# zx81_SD_12_smd.net
KiCad netlist of a schematic drawn in EAGLE
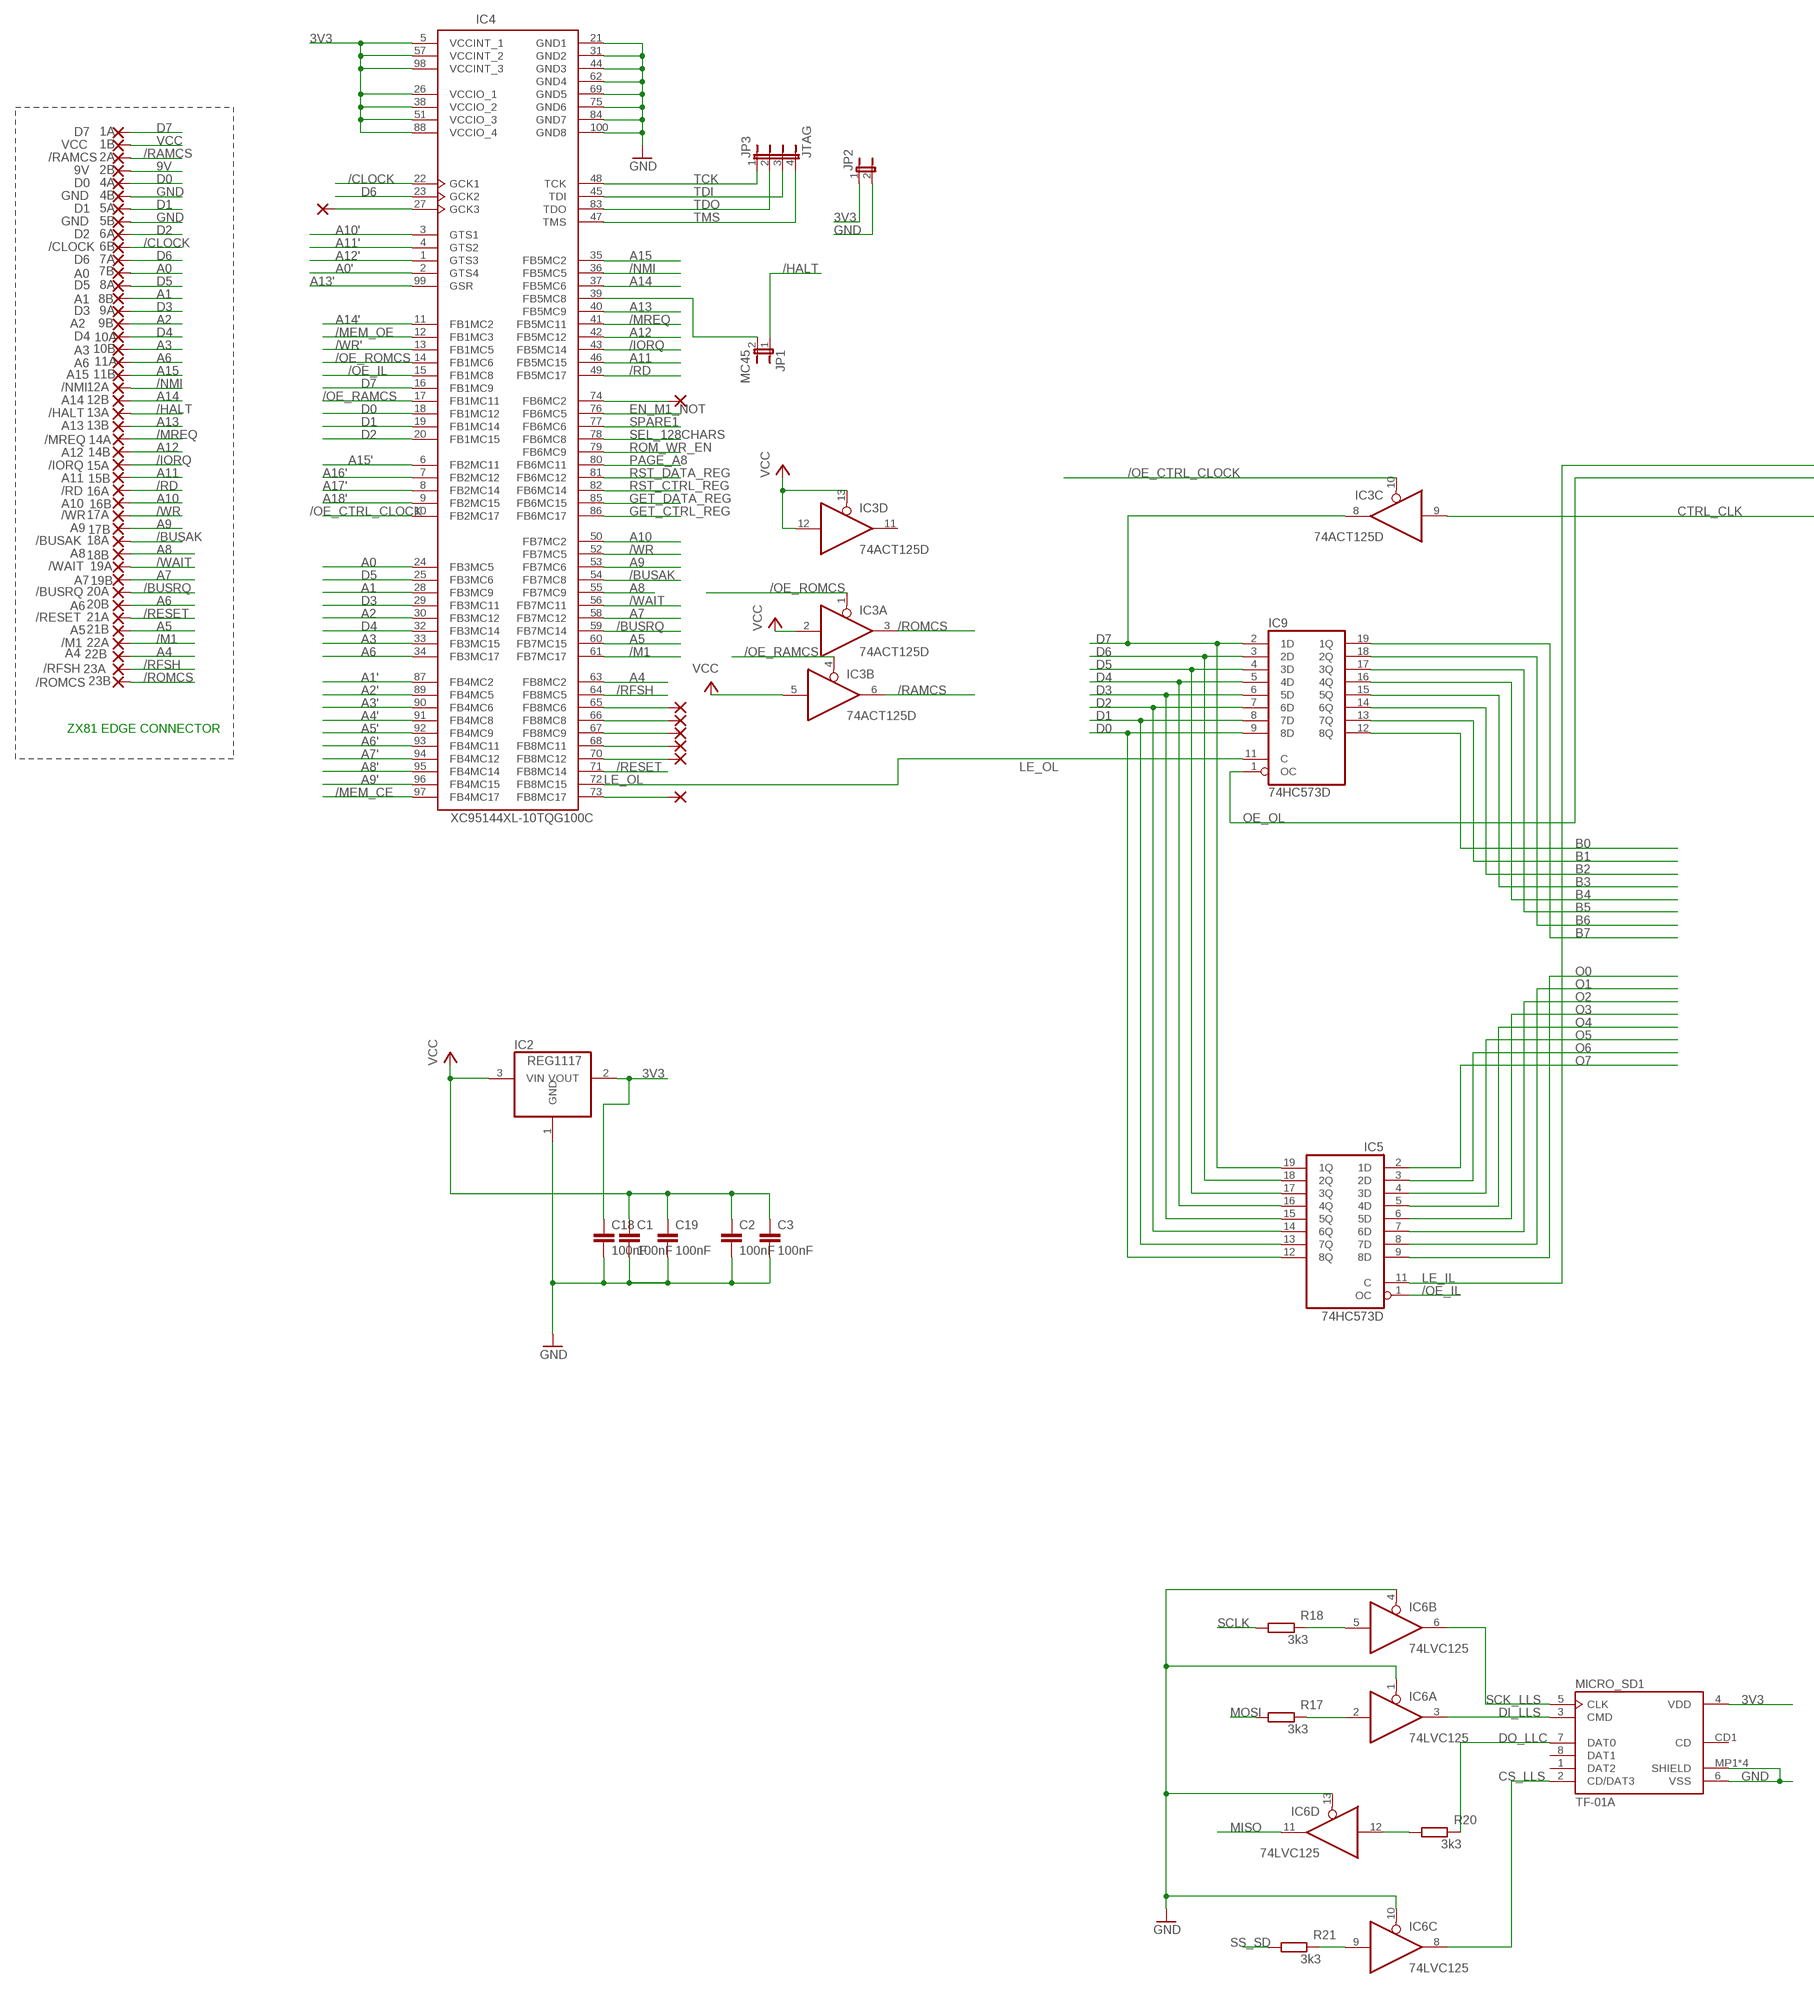
[diagram p0: schematic, sheet 1, part 1 of 2]
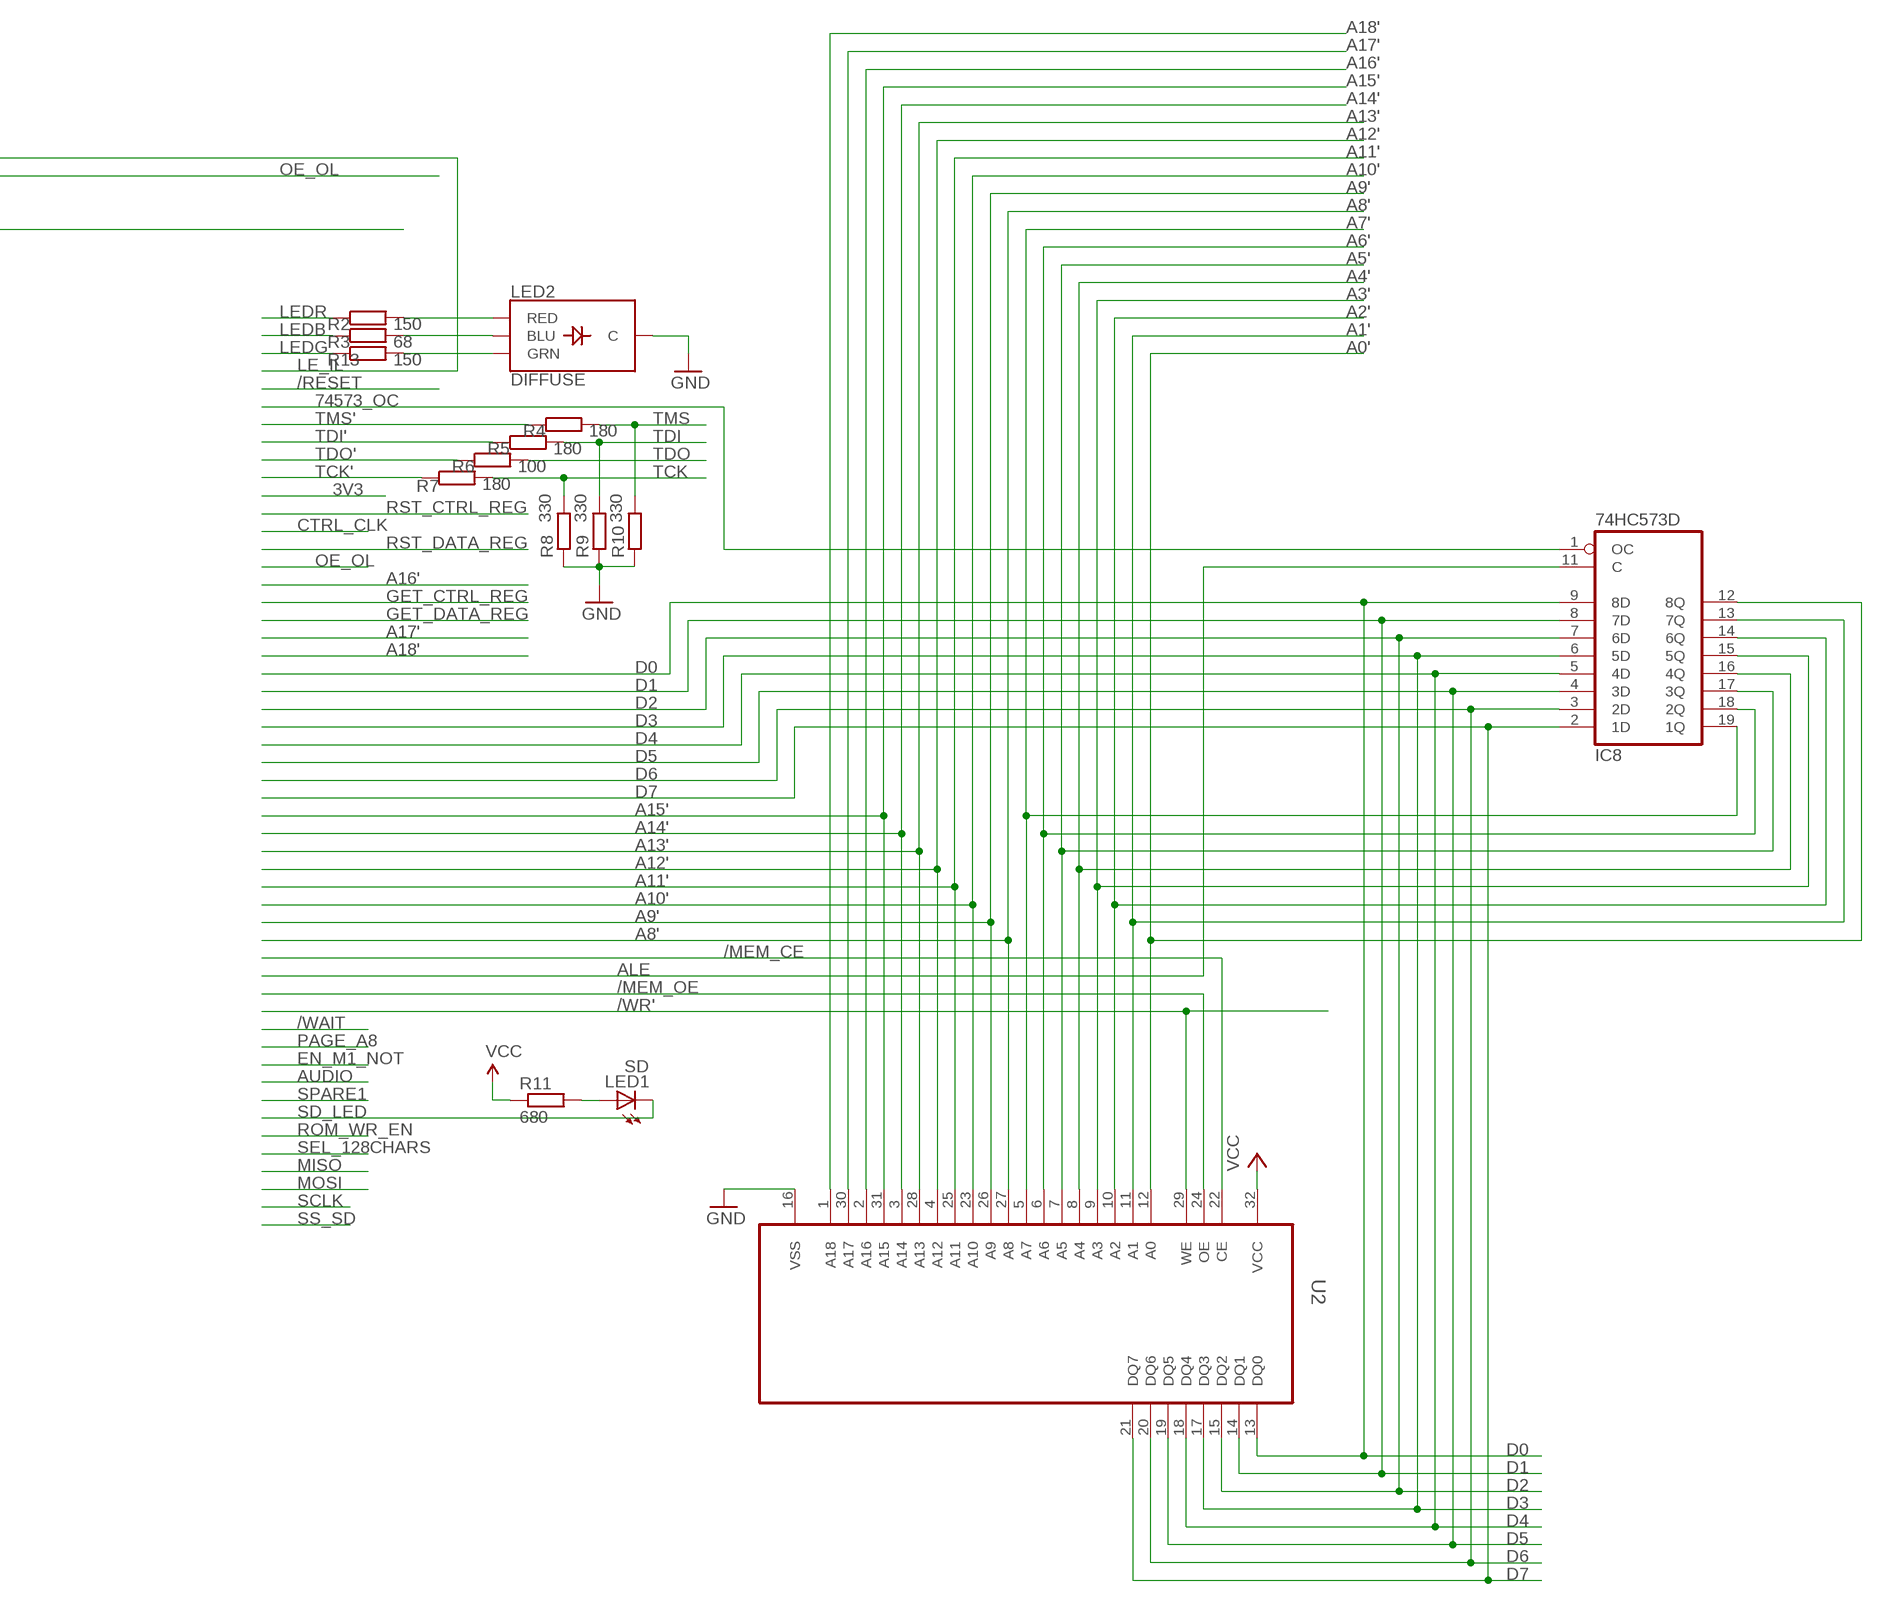
[diagram p1: schematic, sheet 1, part 2 of 2]
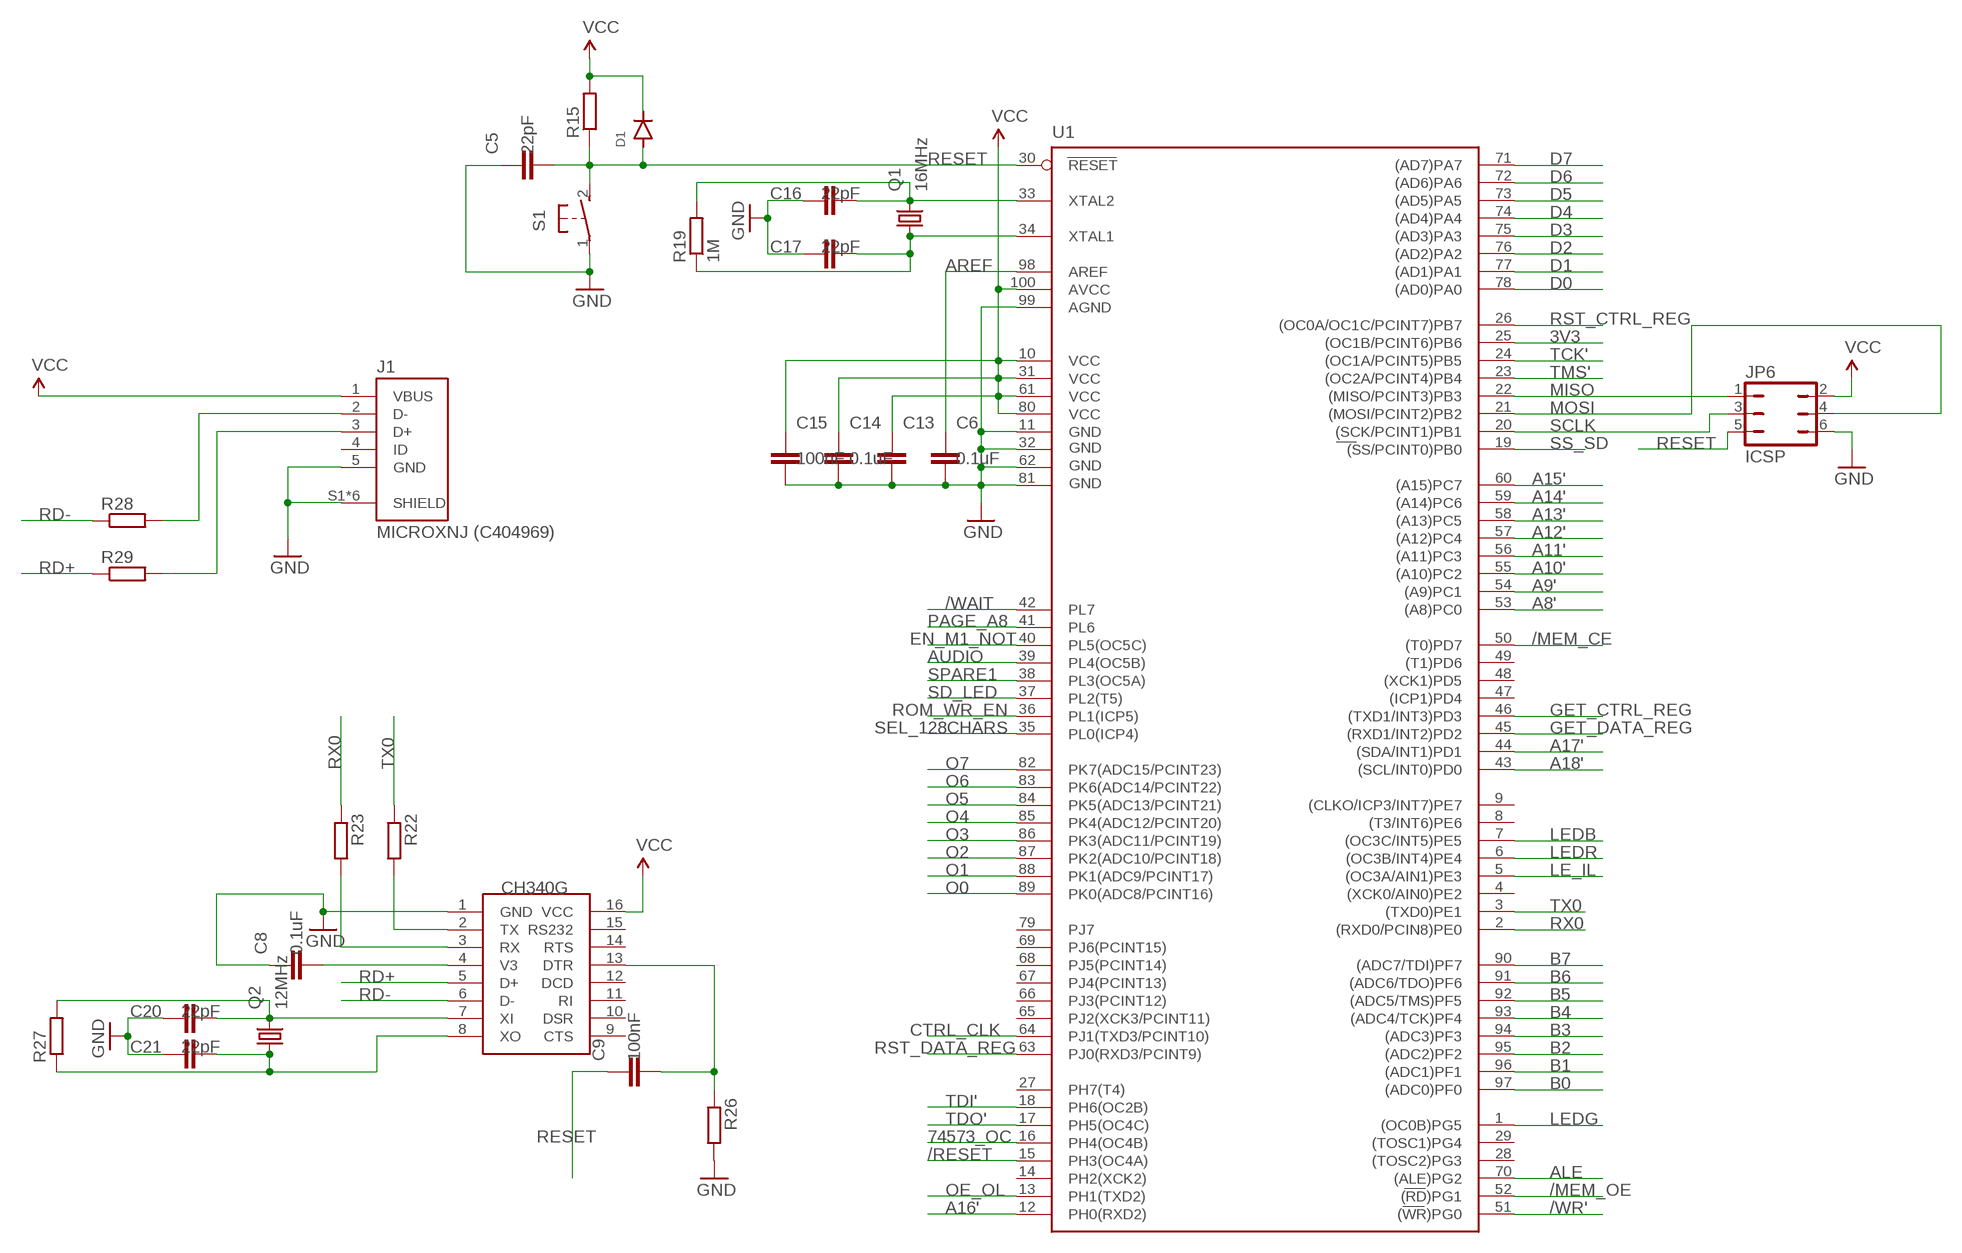
[diagram p2: schematic, sheet 2]

(export (version "E")
  (design (tool "Eeschema 10.0.6"))
  (components
    (comp (ref "1A")
      (value "D7")
      (footprint "eagle-import:EDGEPIN")
      (libsource (lib "eagle-import") (part "SMD2EDGEPIN"))
    )
    (comp (ref "1B")
      (value "VCC")
      (footprint "eagle-import:EDGEPIN")
      (libsource (lib "eagle-import") (part "SMD2EDGEPIN"))
    )
    (comp (ref "2A")
      (value "/RAMCS")
      (footprint "eagle-import:EDGEPIN")
      (libsource (lib "eagle-import") (part "SMD2EDGEPIN"))
    )
    (comp (ref "2B")
      (value "9V")
      (footprint "eagle-import:EDGEPIN")
      (libsource (lib "eagle-import") (part "SMD2EDGEPIN"))
    )
    (comp (ref "4A")
      (value "D0")
      (footprint "eagle-import:EDGEPIN")
      (libsource (lib "eagle-import") (part "SMD2EDGEPIN"))
    )
    (comp (ref "4B")
      (value "GND")
      (footprint "eagle-import:EDGEPIN")
      (libsource (lib "eagle-import") (part "SMD2EDGEPIN"))
    )
    (comp (ref "5A")
      (value "D1")
      (footprint "eagle-import:EDGEPIN")
      (libsource (lib "eagle-import") (part "SMD2EDGEPIN"))
    )
    (comp (ref "5B")
      (value "GND")
      (footprint "eagle-import:EDGEPIN")
      (libsource (lib "eagle-import") (part "SMD2EDGEPIN"))
    )
    (comp (ref "6A")
      (value "D2")
      (footprint "eagle-import:EDGEPIN")
      (libsource (lib "eagle-import") (part "SMD2EDGEPIN"))
    )
    (comp (ref "6B")
      (value "/CLOCK")
      (footprint "eagle-import:EDGEPIN")
      (libsource (lib "eagle-import") (part "SMD2EDGEPIN"))
    )
    (comp (ref "7A")
      (value "D6")
      (footprint "eagle-import:EDGEPIN")
      (libsource (lib "eagle-import") (part "SMD2EDGEPIN"))
    )
    (comp (ref "7B")
      (value "A0")
      (footprint "eagle-import:EDGEPIN")
      (libsource (lib "eagle-import") (part "SMD2EDGEPIN"))
    )
    (comp (ref "8A")
      (value "D5")
      (footprint "eagle-import:EDGEPIN")
      (libsource (lib "eagle-import") (part "SMD2EDGEPIN"))
    )
    (comp (ref "8B")
      (value "A1")
      (footprint "eagle-import:EDGEPIN")
      (libsource (lib "eagle-import") (part "SMD2EDGEPIN"))
    )
    (comp (ref "9A")
      (value "D3")
      (footprint "eagle-import:EDGEPIN")
      (libsource (lib "eagle-import") (part "SMD2EDGEPIN"))
    )
    (comp (ref "9B")
      (value "A2")
      (footprint "eagle-import:EDGEPIN")
      (libsource (lib "eagle-import") (part "SMD2EDGEPIN"))
    )
    (comp (ref "10A")
      (value "D4")
      (footprint "eagle-import:EDGEPIN")
      (libsource (lib "eagle-import") (part "SMD2EDGEPIN"))
    )
    (comp (ref "10B")
      (value "A3")
      (footprint "eagle-import:EDGEPIN")
      (libsource (lib "eagle-import") (part "SMD2EDGEPIN"))
    )
    (comp (ref "11A")
      (value "A6")
      (footprint "eagle-import:EDGEPIN")
      (libsource (lib "eagle-import") (part "SMD2EDGEPIN"))
    )
    (comp (ref "11B")
      (value "A15")
      (footprint "eagle-import:EDGEPIN")
      (libsource (lib "eagle-import") (part "SMD2EDGEPIN"))
    )
    (comp (ref "12A")
      (value "/NMI")
      (footprint "eagle-import:EDGEPIN")
      (libsource (lib "eagle-import") (part "SMD2EDGEPIN"))
    )
    (comp (ref "12B")
      (value "A14")
      (footprint "eagle-import:EDGEPIN")
      (libsource (lib "eagle-import") (part "SMD2EDGEPIN"))
    )
    (comp (ref "13A")
      (value "/HALT")
      (footprint "eagle-import:EDGEPIN")
      (libsource (lib "eagle-import") (part "SMD2EDGEPIN"))
    )
    (comp (ref "13B")
      (value "A13")
      (footprint "eagle-import:EDGEPIN")
      (libsource (lib "eagle-import") (part "SMD2EDGEPIN"))
    )
    (comp (ref "14A")
      (value "/MREQ")
      (footprint "eagle-import:EDGEPIN")
      (libsource (lib "eagle-import") (part "SMD2EDGEPIN"))
    )
    (comp (ref "14B")
      (value "A12")
      (footprint "eagle-import:EDGEPIN")
      (libsource (lib "eagle-import") (part "SMD2EDGEPIN"))
    )
    (comp (ref "15A")
      (value "/IORQ")
      (footprint "eagle-import:EDGEPIN")
      (libsource (lib "eagle-import") (part "SMD2EDGEPIN"))
    )
    (comp (ref "15B")
      (value "A11")
      (footprint "eagle-import:EDGEPIN")
      (libsource (lib "eagle-import") (part "SMD2EDGEPIN"))
    )
    (comp (ref "16A")
      (value "/RD")
      (footprint "eagle-import:EDGEPIN")
      (libsource (lib "eagle-import") (part "SMD2EDGEPIN"))
    )
    (comp (ref "16B")
      (value "A10")
      (footprint "eagle-import:EDGEPIN")
      (libsource (lib "eagle-import") (part "SMD2EDGEPIN"))
    )
    (comp (ref "17A")
      (value "/WR")
      (footprint "eagle-import:EDGEPIN")
      (libsource (lib "eagle-import") (part "SMD2EDGEPIN"))
    )
    (comp (ref "17B")
      (value "A9")
      (footprint "eagle-import:EDGEPIN")
      (libsource (lib "eagle-import") (part "SMD2EDGEPIN"))
    )
    (comp (ref "18A")
      (value "/BUSAK")
      (footprint "eagle-import:EDGEPIN")
      (libsource (lib "eagle-import") (part "SMD2EDGEPIN"))
    )
    (comp (ref "18B")
      (value "A8")
      (footprint "eagle-import:EDGEPIN")
      (libsource (lib "eagle-import") (part "SMD2EDGEPIN"))
    )
    (comp (ref "19A")
      (value "/WAIT")
      (footprint "eagle-import:EDGEPIN")
      (libsource (lib "eagle-import") (part "SMD2EDGEPIN"))
    )
    (comp (ref "19B")
      (value "A7")
      (footprint "eagle-import:EDGEPIN")
      (libsource (lib "eagle-import") (part "SMD2EDGEPIN"))
    )
    (comp (ref "20A")
      (value "/BUSRQ")
      (footprint "eagle-import:EDGEPIN")
      (libsource (lib "eagle-import") (part "SMD2EDGEPIN"))
    )
    (comp (ref "20B")
      (value "A6")
      (footprint "eagle-import:EDGEPIN")
      (libsource (lib "eagle-import") (part "SMD2EDGEPIN"))
    )
    (comp (ref "21A")
      (value "/RESET")
      (footprint "eagle-import:EDGEPIN")
      (libsource (lib "eagle-import") (part "SMD2EDGEPIN"))
    )
    (comp (ref "21B")
      (value "A5")
      (footprint "eagle-import:EDGEPIN")
      (libsource (lib "eagle-import") (part "SMD2EDGEPIN"))
    )
    (comp (ref "22A")
      (value "/M1")
      (footprint "eagle-import:EDGEPIN")
      (libsource (lib "eagle-import") (part "SMD2EDGEPIN"))
    )
    (comp (ref "22B")
      (value "A4")
      (footprint "eagle-import:EDGEPIN")
      (libsource (lib "eagle-import") (part "SMD2EDGEPIN"))
    )
    (comp (ref "23A")
      (value "/RFSH")
      (footprint "eagle-import:EDGEPIN")
      (libsource (lib "eagle-import") (part "SMD2EDGEPIN"))
    )
    (comp (ref "23B")
      (value "/ROMCS")
      (footprint "eagle-import:EDGEPIN")
      (libsource (lib "eagle-import") (part "SMD2EDGEPIN"))
    )
    (comp (ref "C1")
      (value "100nF")
      (footprint "eagle-import:C0603")
      (libsource (lib "eagle-import") (part "C-EUC0603"))
    )
    (comp (ref "C2")
      (value "100nF")
      (footprint "eagle-import:C0603")
      (libsource (lib "eagle-import") (part "C-EUC0603"))
    )
    (comp (ref "C3")
      (value "100nF")
      (footprint "eagle-import:C0603")
      (libsource (lib "eagle-import") (part "C-EUC0603"))
    )
    (comp (ref "C18")
      (value "100nF")
      (footprint "eagle-import:C0603")
      (libsource (lib "eagle-import") (part "C-EUC0603"))
    )
    (comp (ref "C19")
      (value "100nF")
      (footprint "eagle-import:C0603")
      (libsource (lib "eagle-import") (part "C-EUC0603"))
    )
    (comp (ref "IC2")
      (value "REG1117")
      (footprint "eagle-import:SOT223")
      (libsource (lib "eagle-import") (part "REG1117"))
    )
    (comp (ref "IC3")
      (value "74ACT125D")
      (footprint "eagle-import:SO14")
      (libsource (lib "eagle-import") (part "74125DACT"))
    )
    (comp (ref "IC4")
      (value "XC95144XL-10TQG100C")
      (footprint "eagle-import:TQFP100")
      (fields (field (name "MF") "Xilinx Inc."))
      (libsource (lib "eagle-import") (part "XC95144XL-10TQG100C"))
    )
    (comp (ref "IC5")
      (value "74HC573D")
      (footprint "eagle-import:SO20W")
      (libsource (lib "eagle-import") (part "74573DHC"))
    )
    (comp (ref "IC6")
      (value "74LVC125")
      (footprint "eagle-import:SO14")
      (libsource (lib "eagle-import") (part "74125DLS"))
    )
    (comp (ref "IC8")
      (value "74HC573D")
      (footprint "eagle-import:SO20W")
      (libsource (lib "eagle-import") (part "74573DHC"))
    )
    (comp (ref "IC9")
      (value "74HC573D")
      (footprint "eagle-import:SO20W")
      (libsource (lib "eagle-import") (part "74573DHC"))
    )
    (comp (ref "JP1")
      (value "MC45")
      (footprint "eagle-import:JP1")
      (libsource (lib "eagle-import") (part "JP1E"))
    )
    (comp (ref "JP2")
      (value "JP1E")
      (footprint "eagle-import:JP1")
      (libsource (lib "eagle-import") (part "JP1E"))
    )
    (comp (ref "JP3")
      (value "JTAG")
      (footprint "eagle-import:JP4")
      (libsource (lib "eagle-import") (part "JP4E"))
    )
    (comp (ref "LED1")
      (value "SD")
      (footprint "eagle-import:LED5MM")
      (libsource (lib "eagle-import") (part "LED5MM"))
    )
    (comp (ref "LED2")
      (value "DIFFUSE")
      (footprint "eagle-import:LED-RGB-THRU")
      (libsource (lib "eagle-import") (part "LED-RGB-CCDIFFUSE"))
    )
    (comp (ref "MICRO_SD1")
      (value "TF-01A")
      (footprint "eagle-import:TF-01A")
      (fields (field (name "MF") "HRO Electronics Co., Ltd."))
      (libsource (lib "eagle-import") (part "TF-01A"))
    )
    (comp (ref "PAD1")
      (value "1,6/0,8")
      (footprint "eagle-import:1,6_0,8")
      (libsource (lib "eagle-import") (part "1,6/0,8"))
    )
    (comp (ref "PAD2")
      (value "1,6/0,8")
      (footprint "eagle-import:1,6_0,8")
      (libsource (lib "eagle-import") (part "1,6/0,8"))
    )
    (comp (ref "PAD3")
      (value "1,6/0,8")
      (footprint "eagle-import:1,6_0,8")
      (libsource (lib "eagle-import") (part "1,6/0,8"))
    )
    (comp (ref "PAD4")
      (value "1,6/0,8")
      (footprint "eagle-import:1,6_0,8")
      (libsource (lib "eagle-import") (part "1,6/0,8"))
    )
    (comp (ref "PAD5")
      (value "1,6/0,8")
      (footprint "eagle-import:1,6_0,8")
      (libsource (lib "eagle-import") (part "1,6/0,8"))
    )
    (comp (ref "PAD6")
      (value "1,6/0,8")
      (footprint "eagle-import:1,6_0,8")
      (libsource (lib "eagle-import") (part "1,6/0,8"))
    )
    (comp (ref "PAD7")
      (value "1,6/0,8")
      (footprint "eagle-import:1,6_0,8")
      (libsource (lib "eagle-import") (part "1,6/0,8"))
    )
    (comp (ref "PAD8")
      (value "1,6/0,8")
      (footprint "eagle-import:1,6_0,8")
      (libsource (lib "eagle-import") (part "1,6/0,8"))
    )
    (comp (ref "R2")
      (value "150")
      (footprint "eagle-import:R0603")
      (libsource (lib "eagle-import") (part "rcl_334_R-EU_R0603"))
    )
    (comp (ref "R3")
      (value "68")
      (footprint "eagle-import:R0603")
      (libsource (lib "eagle-import") (part "rcl_334_R-EU_R0603"))
    )
    (comp (ref "R4")
      (value "180")
      (footprint "eagle-import:R0603")
      (libsource (lib "eagle-import") (part "rcl_334_R-EU_R0603"))
    )
    (comp (ref "R5")
      (value "180")
      (footprint "eagle-import:R0603")
      (libsource (lib "eagle-import") (part "rcl_334_R-EU_R0603"))
    )
    (comp (ref "R6")
      (value "100")
      (footprint "eagle-import:R0603")
      (libsource (lib "eagle-import") (part "rcl_334_R-EU_R0603"))
    )
    (comp (ref "R7")
      (value "180")
      (footprint "eagle-import:R0603")
      (libsource (lib "eagle-import") (part "rcl_334_R-EU_R0603"))
    )
    (comp (ref "R8")
      (value "330")
      (footprint "eagle-import:R0603")
      (libsource (lib "eagle-import") (part "rcl_334_R-EU_R0603"))
    )
    (comp (ref "R9")
      (value "330")
      (footprint "eagle-import:R0603")
      (libsource (lib "eagle-import") (part "rcl_334_R-EU_R0603"))
    )
    (comp (ref "R10")
      (value "330")
      (footprint "eagle-import:R0603")
      (libsource (lib "eagle-import") (part "rcl_334_R-EU_R0603"))
    )
    (comp (ref "R11")
      (value "680")
      (footprint "eagle-import:R0603")
      (libsource (lib "eagle-import") (part "R-EU_R0603"))
    )
    (comp (ref "R13")
      (value "150")
      (footprint "eagle-import:R0603")
      (libsource (lib "eagle-import") (part "rcl_334_R-EU_R0603"))
    )
    (comp (ref "R17")
      (value "3k3")
      (footprint "eagle-import:R0603")
      (libsource (lib "eagle-import") (part "R-EU_R0603"))
    )
    (comp (ref "R18")
      (value "3k3")
      (footprint "eagle-import:R0603")
      (libsource (lib "eagle-import") (part "R-EU_R0603"))
    )
    (comp (ref "R20")
      (value "3k3")
      (footprint "eagle-import:R0603")
      (libsource (lib "eagle-import") (part "R-EU_R0603"))
    )
    (comp (ref "R21")
      (value "3k3")
      (footprint "eagle-import:R0603")
      (libsource (lib "eagle-import") (part "R-EU_R0603"))
    )
    (comp (ref "U2")
      (value "AS6C4008-55SINSOP5")
      (footprint "eagle-import:SOP32-5")
      (libsource (lib "eagle-import") (part "AS6C4008-55SINSOP5"))
    )
    (comp (ref "C5")
      (value "22pF")
      (footprint "eagle-import:C0603")
      (libsource (lib "eagle-import") (part "C-EUC0603"))
    )
    (comp (ref "C6")
      (value "0.1uF")
      (footprint "eagle-import:C0603")
      (libsource (lib "eagle-import") (part "C-EUC0603"))
    )
    (comp (ref "C8")
      (value "0.1uF")
      (footprint "eagle-import:C0603")
      (libsource (lib "eagle-import") (part "C-EUC0603"))
    )
    (comp (ref "C9")
      (value "100nF")
      (footprint "eagle-import:C0603")
      (libsource (lib "eagle-import") (part "C-EUC0603"))
    )
    (comp (ref "C13")
      (value "0.1uF")
      (footprint "eagle-import:C0603")
      (libsource (lib "eagle-import") (part "C-EUC0603"))
    )
    (comp (ref "C14")
      (value "0.1uF")
      (footprint "eagle-import:C0603")
      (libsource (lib "eagle-import") (part "C-EUC0603"))
    )
    (comp (ref "C15")
      (value "100nF")
      (footprint "eagle-import:C0603")
      (libsource (lib "eagle-import") (part "C-EUC0603"))
    )
    (comp (ref "C16")
      (value "22pF")
      (footprint "eagle-import:C0603")
      (libsource (lib "eagle-import") (part "C-EUC0603"))
    )
    (comp (ref "C17")
      (value "22pF")
      (footprint "eagle-import:C0603")
      (libsource (lib "eagle-import") (part "C-EUC0603"))
    )
    (comp (ref "C20")
      (value "22pF")
      (footprint "eagle-import:C0603")
      (libsource (lib "eagle-import") (part "C-EUC0603"))
    )
    (comp (ref "C21")
      (value "22pF")
      (footprint "eagle-import:C0603")
      (libsource (lib "eagle-import") (part "C-EUC0603"))
    )
    (comp (ref "D1")
      (value "DIODE-SOD123")
      (footprint "eagle-import:SOD123")
      (libsource (lib "eagle-import") (part "DIODE-SOD123"))
    )
    (comp (ref "IC7")
      (value "CH340G")
      (footprint "eagle-import:SOIC16")
      (libsource (lib "eagle-import") (part "CH340G"))
    )
    (comp (ref "J1")
      (value "MICROXNJ (C404969)")
      (footprint "eagle-import:SHOUHAN_MICROXNJ")
      (fields (field (name "MF") "Shouhan") (field (name "MP") "MICROXNJ"))
      (libsource (lib "eagle-import") (part "MICROXNJ"))
    )
    (comp (ref "JP6")
      (value "ICSP")
      (footprint "eagle-import:JP3Q")
      (libsource (lib "eagle-import") (part "JP3Q"))
    )
    (comp (ref "Q1")
      (value "16MHz")
      (footprint "eagle-import:3.2X2.5_KX-7")
      (libsource (lib "eagle-import") (part "KX-7"))
    )
    (comp (ref "Q2")
      (value "12MHz")
      (footprint "eagle-import:3.2X2.5_KX-7")
      (libsource (lib "eagle-import") (part "KX-7"))
    )
    (comp (ref "R15")
      (value "R-EU_R0603")
      (footprint "eagle-import:R0603")
      (libsource (lib "eagle-import") (part "rcl_334_R-EU_R0603"))
    )
    (comp (ref "R19")
      (value "1M")
      (footprint "eagle-import:R0603")
      (libsource (lib "eagle-import") (part "rcl_334_R-EU_R0603"))
    )
    (comp (ref "R22")
      (value "1K")
      (footprint "eagle-import:R0603")
      (libsource (lib "eagle-import") (part "rcl_334_R-EU_R0603"))
    )
    (comp (ref "R23")
      (value "1K")
      (footprint "eagle-import:R0603")
      (libsource (lib "eagle-import") (part "rcl_334_R-EU_R0603"))
    )
    (comp (ref "R26")
      (value "1K")
      (footprint "eagle-import:R0603")
      (libsource (lib "eagle-import") (part "rcl_334_R-EU_R0603"))
    )
    (comp (ref "R27")
      (value "1M")
      (footprint "eagle-import:R0603")
      (libsource (lib "eagle-import") (part "rcl_334_R-EU_R0603"))
    )
    (comp (ref "R28")
      (value "22R")
      (footprint "eagle-import:R0603")
      (libsource (lib "eagle-import") (part "rcl_334_R-EU_R0603"))
    )
    (comp (ref "R29")
      (value "22R")
      (footprint "eagle-import:R0603")
      (libsource (lib "eagle-import") (part "rcl_334_R-EU_R0603"))
    )
    (comp (ref "S1")
      (value "31-XX")
      (footprint "eagle-import:B3F-31XX")
      (fields (field (name "MPN") "B3F-3100"))
      (libsource (lib "eagle-import") (part "31-XX"))
    )
    (comp (ref "U1")
      (value "ATMEGA2560AU")
      (footprint "eagle-import:TQFP100")
      (libsource (lib "eagle-import") (part "ATMEGA2560AU"))
    )
  )
  (nets
    (net (code "1") (name "3V3") (class "Default")
      (node (ref "C18") (pin "1") (pinfunction "1_1") (pintype "passive"))
      (node (ref "IC2") (pin "2") (pinfunction "VOUT_2") (pintype "output"))
      (node (ref "IC4") (pin "26") (pinfunction "VCCIO_1_26") (pintype "power_in"))
      (node (ref "IC4") (pin "38") (pinfunction "VCCIO_2_38") (pintype "power_in"))
      (node (ref "IC4") (pin "5") (pinfunction "VCCINT_1_5") (pintype "power_in"))
      (node (ref "IC4") (pin "51") (pinfunction "VCCIO_3_51") (pintype "power_in"))
      (node (ref "IC4") (pin "57") (pinfunction "VCCINT_2_57") (pintype "power_in"))
      (node (ref "IC4") (pin "88") (pinfunction "VCCIO_4_88") (pintype "power_in"))
      (node (ref "IC4") (pin "98") (pinfunction "VCCINT_3_98") (pintype "power_in"))
      (node (ref "JP2") (pin "1") (pinfunction "1_1") (pintype "passive"))
      (node (ref "MICRO_SD1") (pin "4") (pinfunction "VDD_4") (pintype "power_in"))
      (node (ref "U1") (pin "25") (pinfunction "(OC1B/PCINT6)PB6_25") (pintype "bidirectional"))
    )
    (net (code "2") (name "9V") (class "Default")
      (node (ref "2B") (pin "1") (pinfunction "P_1") (pintype "passive"))
    )
    (net (code "3") (name "74573_OC") (class "Default")
      (node (ref "IC8") (pin "1") (pinfunction "OC_1") (pintype "input"))
      (node (ref "U1") (pin "16") (pinfunction "PH4(OC4B)_16") (pintype "bidirectional"))
    )
    (net (code "4") (name "A0") (class "Default")
      (node (ref "7B") (pin "1") (pinfunction "P_1") (pintype "passive"))
      (node (ref "IC4") (pin "24") (pinfunction "FB3MC5_24") (pintype "bidirectional"))
    )
    (net (code "5") (name "A0'") (class "Default")
      (node (ref "IC4") (pin "2") (pinfunction "GTS4_2") (pintype "bidirectional"))
      (node (ref "IC8") (pin "12") (pinfunction "8Q_12") (pintype "tri_state"))
      (node (ref "U2") (pin "12") (pinfunction "A0_12") (pintype "input"))
    )
    (net (code "6") (name "A1") (class "Default")
      (node (ref "8B") (pin "1") (pinfunction "P_1") (pintype "passive"))
      (node (ref "IC4") (pin "28") (pinfunction "FB3MC9_28") (pintype "bidirectional"))
    )
    (net (code "7") (name "A1'") (class "Default")
      (node (ref "IC4") (pin "87") (pinfunction "FB4MC2_87") (pintype "bidirectional"))
      (node (ref "IC8") (pin "13") (pinfunction "7Q_13") (pintype "tri_state"))
      (node (ref "U2") (pin "11") (pinfunction "A1_11") (pintype "input"))
    )
    (net (code "8") (name "A2") (class "Default")
      (node (ref "9B") (pin "1") (pinfunction "P_1") (pintype "passive"))
      (node (ref "IC4") (pin "30") (pinfunction "FB3MC12_30") (pintype "bidirectional"))
    )
    (net (code "9") (name "A2'") (class "Default")
      (node (ref "IC4") (pin "89") (pinfunction "FB4MC5_89") (pintype "bidirectional"))
      (node (ref "IC8") (pin "14") (pinfunction "6Q_14") (pintype "tri_state"))
      (node (ref "U2") (pin "10") (pinfunction "A2_10") (pintype "input"))
    )
    (net (code "10") (name "A3") (class "Default")
      (node (ref "10B") (pin "1") (pinfunction "P_1") (pintype "passive"))
      (node (ref "IC4") (pin "33") (pinfunction "FB3MC15_33") (pintype "bidirectional"))
    )
    (net (code "11") (name "A3'") (class "Default")
      (node (ref "IC4") (pin "90") (pinfunction "FB4MC6_90") (pintype "bidirectional"))
      (node (ref "IC8") (pin "15") (pinfunction "5Q_15") (pintype "tri_state"))
      (node (ref "U2") (pin "9") (pinfunction "A3_9") (pintype "input"))
    )
    (net (code "12") (name "A4") (class "Default")
      (node (ref "22B") (pin "1") (pinfunction "P_1") (pintype "passive"))
      (node (ref "IC4") (pin "63") (pinfunction "FB8MC2_63") (pintype "bidirectional"))
    )
    (net (code "13") (name "A4'") (class "Default")
      (node (ref "IC4") (pin "91") (pinfunction "FB4MC8_91") (pintype "bidirectional"))
      (node (ref "IC8") (pin "16") (pinfunction "4Q_16") (pintype "tri_state"))
      (node (ref "U2") (pin "8") (pinfunction "A4_8") (pintype "input"))
    )
    (net (code "14") (name "A5") (class "Default")
      (node (ref "21B") (pin "1") (pinfunction "P_1") (pintype "passive"))
      (node (ref "IC4") (pin "60") (pinfunction "FB7MC15_60") (pintype "bidirectional"))
    )
    (net (code "15") (name "A5'") (class "Default")
      (node (ref "IC4") (pin "92") (pinfunction "FB4MC9_92") (pintype "bidirectional"))
      (node (ref "IC8") (pin "17") (pinfunction "3Q_17") (pintype "tri_state"))
      (node (ref "U2") (pin "7") (pinfunction "A5_7") (pintype "input"))
    )
    (net (code "16") (name "A6") (class "Default")
      (node (ref "11A") (pin "1") (pinfunction "P_1") (pintype "passive"))
      (node (ref "20B") (pin "1") (pinfunction "P_1") (pintype "passive"))
      (node (ref "IC4") (pin "34") (pinfunction "FB3MC17_34") (pintype "bidirectional"))
    )
    (net (code "17") (name "A6'") (class "Default")
      (node (ref "IC4") (pin "93") (pinfunction "FB4MC11_93") (pintype "bidirectional"))
      (node (ref "IC8") (pin "18") (pinfunction "2Q_18") (pintype "tri_state"))
      (node (ref "U2") (pin "6") (pinfunction "A6_6") (pintype "input"))
    )
    (net (code "18") (name "A7") (class "Default")
      (node (ref "19B") (pin "1") (pinfunction "P_1") (pintype "passive"))
      (node (ref "IC4") (pin "58") (pinfunction "FB7MC12_58") (pintype "bidirectional"))
    )
    (net (code "19") (name "A7'") (class "Default")
      (node (ref "IC4") (pin "94") (pinfunction "FB4MC12_94") (pintype "bidirectional"))
      (node (ref "IC8") (pin "19") (pinfunction "1Q_19") (pintype "tri_state"))
      (node (ref "U2") (pin "5") (pinfunction "A7_5") (pintype "input"))
    )
    (net (code "20") (name "A8") (class "Default")
      (node (ref "18B") (pin "1") (pinfunction "P_1") (pintype "passive"))
      (node (ref "IC4") (pin "55") (pinfunction "FB7MC9_55") (pintype "bidirectional"))
    )
    (net (code "21") (name "A8'") (class "Default")
      (node (ref "IC4") (pin "95") (pinfunction "FB4MC14_95") (pintype "bidirectional"))
      (node (ref "U1") (pin "53") (pinfunction "(A8)PC0_53") (pintype "bidirectional"))
      (node (ref "U2") (pin "27") (pinfunction "A8_27") (pintype "input"))
    )
    (net (code "22") (name "A9") (class "Default")
      (node (ref "17B") (pin "1") (pinfunction "P_1") (pintype "passive"))
      (node (ref "IC4") (pin "53") (pinfunction "FB7MC6_53") (pintype "bidirectional"))
    )
    (net (code "23") (name "A9'") (class "Default")
      (node (ref "IC4") (pin "96") (pinfunction "FB4MC15_96") (pintype "bidirectional"))
      (node (ref "U1") (pin "54") (pinfunction "(A9)PC1_54") (pintype "bidirectional"))
      (node (ref "U2") (pin "26") (pinfunction "A9_26") (pintype "input"))
    )
    (net (code "24") (name "A10") (class "Default")
      (node (ref "16B") (pin "1") (pinfunction "P_1") (pintype "passive"))
      (node (ref "IC4") (pin "50") (pinfunction "FB7MC2_50") (pintype "bidirectional"))
    )
    (net (code "25") (name "A10'") (class "Default")
      (node (ref "IC4") (pin "3") (pinfunction "GTS1_3") (pintype "bidirectional"))
      (node (ref "U1") (pin "55") (pinfunction "(A10)PC2_55") (pintype "bidirectional"))
      (node (ref "U2") (pin "23") (pinfunction "A10_23") (pintype "input"))
    )
    (net (code "26") (name "A11") (class "Default")
      (node (ref "15B") (pin "1") (pinfunction "P_1") (pintype "passive"))
      (node (ref "IC4") (pin "46") (pinfunction "FB5MC15_46") (pintype "bidirectional"))
    )
    (net (code "27") (name "A11'") (class "Default")
      (node (ref "IC4") (pin "4") (pinfunction "GTS2_4") (pintype "bidirectional"))
      (node (ref "U1") (pin "56") (pinfunction "(A11)PC3_56") (pintype "bidirectional"))
      (node (ref "U2") (pin "25") (pinfunction "A11_25") (pintype "input"))
    )
    (net (code "28") (name "A12") (class "Default")
      (node (ref "14B") (pin "1") (pinfunction "P_1") (pintype "passive"))
      (node (ref "IC4") (pin "42") (pinfunction "FB5MC12_42") (pintype "bidirectional"))
    )
    (net (code "29") (name "A12'") (class "Default")
      (node (ref "IC4") (pin "1") (pinfunction "GTS3_1") (pintype "bidirectional"))
      (node (ref "U1") (pin "57") (pinfunction "(A12)PC4_57") (pintype "bidirectional"))
      (node (ref "U2") (pin "4") (pinfunction "A12_4") (pintype "input"))
    )
    (net (code "30") (name "A13") (class "Default")
      (node (ref "13B") (pin "1") (pinfunction "P_1") (pintype "passive"))
      (node (ref "IC4") (pin "40") (pinfunction "FB5MC9_40") (pintype "bidirectional"))
    )
    (net (code "31") (name "A13'") (class "Default")
      (node (ref "IC4") (pin "99") (pinfunction "GSR_99") (pintype "bidirectional"))
      (node (ref "U1") (pin "58") (pinfunction "(A13)PC5_58") (pintype "bidirectional"))
      (node (ref "U2") (pin "28") (pinfunction "A13_28") (pintype "input"))
    )
    (net (code "32") (name "A14") (class "Default")
      (node (ref "12B") (pin "1") (pinfunction "P_1") (pintype "passive"))
      (node (ref "IC4") (pin "37") (pinfunction "FB5MC6_37") (pintype "bidirectional"))
    )
    (net (code "33") (name "A14'") (class "Default")
      (node (ref "IC4") (pin "11") (pinfunction "FB1MC2_11") (pintype "bidirectional"))
      (node (ref "U1") (pin "59") (pinfunction "(A14)PC6_59") (pintype "bidirectional"))
      (node (ref "U2") (pin "3") (pinfunction "A14_3") (pintype "input"))
    )
    (net (code "34") (name "A15") (class "Default")
      (node (ref "11B") (pin "1") (pinfunction "P_1") (pintype "passive"))
      (node (ref "IC4") (pin "35") (pinfunction "FB5MC2_35") (pintype "bidirectional"))
    )
    (net (code "35") (name "A15'") (class "Default")
      (node (ref "IC4") (pin "6") (pinfunction "FB2MC11_6") (pintype "bidirectional"))
      (node (ref "U1") (pin "60") (pinfunction "(A15)PC7_60") (pintype "bidirectional"))
      (node (ref "U2") (pin "31") (pinfunction "A15_31") (pintype "input"))
    )
    (net (code "36") (name "A16'") (class "Default")
      (node (ref "IC4") (pin "7") (pinfunction "FB2MC12_7") (pintype "bidirectional"))
      (node (ref "U1") (pin "12") (pinfunction "PH0(RXD2)_12") (pintype "bidirectional"))
      (node (ref "U2") (pin "2") (pinfunction "A16_2") (pintype "input"))
    )
    (net (code "37") (name "A17'") (class "Default")
      (node (ref "IC4") (pin "8") (pinfunction "FB2MC14_8") (pintype "bidirectional"))
      (node (ref "U1") (pin "44") (pinfunction "(SDA/INT1)PD1_44") (pintype "bidirectional"))
      (node (ref "U2") (pin "30") (pinfunction "A17_30") (pintype "input"))
    )
    (net (code "38") (name "A18'") (class "Default")
      (node (ref "IC4") (pin "9") (pinfunction "FB2MC15_9") (pintype "bidirectional"))
      (node (ref "U1") (pin "43") (pinfunction "(SCL/INT0)PD0_43") (pintype "bidirectional"))
      (node (ref "U2") (pin "1") (pinfunction "A18_1") (pintype "input"))
    )
    (net (code "39") (name "ALE") (class "Default")
      (node (ref "IC8") (pin "11") (pinfunction "C_11") (pintype "input"))
      (node (ref "U1") (pin "70") (pinfunction "(ALE)PG2_70") (pintype "bidirectional"))
    )
    (net (code "40") (name "AREF") (class "Default")
      (node (ref "C6") (pin "1") (pinfunction "1_1") (pintype "passive"))
      (node (ref "U1") (pin "98") (pinfunction "AREF_98") (pintype "bidirectional"))
    )
    (net (code "41") (name "AUDIO") (class "Default")
      (node (ref "U1") (pin "39") (pinfunction "PL4(OC5B)_39") (pintype "bidirectional"))
    )
    (net (code "42") (name "B0") (class "Default")
      (node (ref "IC9") (pin "19") (pinfunction "1Q_19") (pintype "tri_state"))
      (node (ref "U1") (pin "97") (pinfunction "(ADC0)PF0_97") (pintype "bidirectional"))
    )
    (net (code "43") (name "B1") (class "Default")
      (node (ref "IC9") (pin "18") (pinfunction "2Q_18") (pintype "tri_state"))
      (node (ref "U1") (pin "96") (pinfunction "(ADC1)PF1_96") (pintype "bidirectional"))
    )
    (net (code "44") (name "B2") (class "Default")
      (node (ref "IC9") (pin "17") (pinfunction "3Q_17") (pintype "tri_state"))
      (node (ref "U1") (pin "95") (pinfunction "(ADC2)PF2_95") (pintype "bidirectional"))
    )
    (net (code "45") (name "B3") (class "Default")
      (node (ref "IC9") (pin "16") (pinfunction "4Q_16") (pintype "tri_state"))
      (node (ref "U1") (pin "94") (pinfunction "(ADC3)PF3_94") (pintype "bidirectional"))
    )
    (net (code "46") (name "B4") (class "Default")
      (node (ref "IC9") (pin "15") (pinfunction "5Q_15") (pintype "tri_state"))
      (node (ref "U1") (pin "93") (pinfunction "(ADC4/TCK)PF4_93") (pintype "bidirectional"))
    )
    (net (code "47") (name "B5") (class "Default")
      (node (ref "IC9") (pin "14") (pinfunction "6Q_14") (pintype "tri_state"))
      (node (ref "U1") (pin "92") (pinfunction "(ADC5/TMS)PF5_92") (pintype "bidirectional"))
    )
    (net (code "48") (name "B6") (class "Default")
      (node (ref "IC9") (pin "13") (pinfunction "7Q_13") (pintype "tri_state"))
      (node (ref "U1") (pin "91") (pinfunction "(ADC6/TDO)PF6_91") (pintype "bidirectional"))
    )
    (net (code "49") (name "B7") (class "Default")
      (node (ref "IC9") (pin "12") (pinfunction "8Q_12") (pintype "tri_state"))
      (node (ref "U1") (pin "90") (pinfunction "(ADC7/TDI)PF7_90") (pintype "bidirectional"))
    )
    (net (code "50") (name "CS_LLS") (class "Default")
      (node (ref "IC6") (pin "8") (pinfunction "O_8") (pintype "tri_state"))
      (node (ref "MICRO_SD1") (pin "2") (pinfunction "CD/DAT3_2") (pintype "bidirectional"))
    )
    (net (code "51") (name "CTRL_CLK") (class "Default")
      (node (ref "IC3") (pin "9") (pinfunction "I_9") (pintype "input"))
      (node (ref "U1") (pin "64") (pinfunction "PJ1(TXD3/PCINT10)_64") (pintype "bidirectional"))
    )
    (net (code "52") (name "D0") (class "Default")
      (node (ref "4A") (pin "1") (pinfunction "P_1") (pintype "passive"))
      (node (ref "IC4") (pin "18") (pinfunction "FB1MC12_18") (pintype "bidirectional"))
      (node (ref "IC5") (pin "12") (pinfunction "8Q_12") (pintype "tri_state"))
      (node (ref "IC8") (pin "9") (pinfunction "8D_9") (pintype "input"))
      (node (ref "IC9") (pin "9") (pinfunction "8D_9") (pintype "input"))
      (node (ref "U1") (pin "78") (pinfunction "(AD0)PA0_78") (pintype "bidirectional"))
      (node (ref "U2") (pin "13") (pinfunction "DQ0_13") (pintype "output"))
    )
    (net (code "53") (name "D1") (class "Default")
      (node (ref "5A") (pin "1") (pinfunction "P_1") (pintype "passive"))
      (node (ref "IC4") (pin "19") (pinfunction "FB1MC14_19") (pintype "bidirectional"))
      (node (ref "IC5") (pin "13") (pinfunction "7Q_13") (pintype "tri_state"))
      (node (ref "IC8") (pin "8") (pinfunction "7D_8") (pintype "input"))
      (node (ref "IC9") (pin "8") (pinfunction "7D_8") (pintype "input"))
      (node (ref "U1") (pin "77") (pinfunction "(AD1)PA1_77") (pintype "bidirectional"))
      (node (ref "U2") (pin "14") (pinfunction "DQ1_14") (pintype "output"))
    )
    (net (code "54") (name "D2") (class "Default")
      (node (ref "6A") (pin "1") (pinfunction "P_1") (pintype "passive"))
      (node (ref "IC4") (pin "20") (pinfunction "FB1MC15_20") (pintype "bidirectional"))
      (node (ref "IC5") (pin "14") (pinfunction "6Q_14") (pintype "tri_state"))
      (node (ref "IC8") (pin "7") (pinfunction "6D_7") (pintype "input"))
      (node (ref "IC9") (pin "7") (pinfunction "6D_7") (pintype "input"))
      (node (ref "U1") (pin "76") (pinfunction "(AD2)PA2_76") (pintype "bidirectional"))
      (node (ref "U2") (pin "15") (pinfunction "DQ2_15") (pintype "output"))
    )
    (net (code "55") (name "D3") (class "Default")
      (node (ref "9A") (pin "1") (pinfunction "P_1") (pintype "passive"))
      (node (ref "IC4") (pin "29") (pinfunction "FB3MC11_29") (pintype "bidirectional"))
      (node (ref "IC5") (pin "15") (pinfunction "5Q_15") (pintype "tri_state"))
      (node (ref "IC8") (pin "6") (pinfunction "5D_6") (pintype "input"))
      (node (ref "IC9") (pin "6") (pinfunction "5D_6") (pintype "input"))
      (node (ref "U1") (pin "75") (pinfunction "(AD3)PA3_75") (pintype "bidirectional"))
      (node (ref "U2") (pin "17") (pinfunction "DQ3_17") (pintype "output"))
    )
    (net (code "56") (name "D4") (class "Default")
      (node (ref "10A") (pin "1") (pinfunction "P_1") (pintype "passive"))
      (node (ref "IC4") (pin "32") (pinfunction "FB3MC14_32") (pintype "bidirectional"))
      (node (ref "IC5") (pin "16") (pinfunction "4Q_16") (pintype "tri_state"))
      (node (ref "IC8") (pin "5") (pinfunction "4D_5") (pintype "input"))
      (node (ref "IC9") (pin "5") (pinfunction "4D_5") (pintype "input"))
      (node (ref "U1") (pin "74") (pinfunction "(AD4)PA4_74") (pintype "bidirectional"))
      (node (ref "U2") (pin "18") (pinfunction "DQ4_18") (pintype "output"))
    )
    (net (code "57") (name "D5") (class "Default")
      (node (ref "8A") (pin "1") (pinfunction "P_1") (pintype "passive"))
      (node (ref "IC4") (pin "25") (pinfunction "FB3MC6_25") (pintype "bidirectional"))
      (node (ref "IC5") (pin "17") (pinfunction "3Q_17") (pintype "tri_state"))
      (node (ref "IC8") (pin "4") (pinfunction "3D_4") (pintype "input"))
      (node (ref "IC9") (pin "4") (pinfunction "3D_4") (pintype "input"))
      (node (ref "U1") (pin "73") (pinfunction "(AD5)PA5_73") (pintype "bidirectional"))
      (node (ref "U2") (pin "19") (pinfunction "DQ5_19") (pintype "output"))
    )
    (net (code "58") (name "D6") (class "Default")
      (node (ref "7A") (pin "1") (pinfunction "P_1") (pintype "passive"))
      (node (ref "IC4") (pin "23") (pinfunction "GCK2_23") (pintype "bidirectional"))
      (node (ref "IC5") (pin "18") (pinfunction "2Q_18") (pintype "tri_state"))
      (node (ref "IC8") (pin "3") (pinfunction "2D_3") (pintype "input"))
      (node (ref "IC9") (pin "3") (pinfunction "2D_3") (pintype "input"))
      (node (ref "U1") (pin "72") (pinfunction "(AD6)PA6_72") (pintype "bidirectional"))
      (node (ref "U2") (pin "20") (pinfunction "DQ6_20") (pintype "output"))
    )
    (net (code "59") (name "D7") (class "Default")
      (node (ref "1A") (pin "1") (pinfunction "P_1") (pintype "passive"))
      (node (ref "IC3") (pin "8") (pinfunction "O_8") (pintype "tri_state"))
      (node (ref "IC4") (pin "16") (pinfunction "FB1MC9_16") (pintype "bidirectional"))
      (node (ref "IC5") (pin "19") (pinfunction "1Q_19") (pintype "tri_state"))
      (node (ref "IC8") (pin "2") (pinfunction "1D_2") (pintype "input"))
      (node (ref "IC9") (pin "2") (pinfunction "1D_2") (pintype "input"))
      (node (ref "U1") (pin "71") (pinfunction "(AD7)PA7_71") (pintype "bidirectional"))
      (node (ref "U2") (pin "21") (pinfunction "DQ7_21") (pintype "output"))
    )
    (net (code "60") (name "DI_LLS") (class "Default")
      (node (ref "IC6") (pin "3") (pinfunction "O_3") (pintype "tri_state"))
      (node (ref "MICRO_SD1") (pin "3") (pinfunction "CMD_3") (pintype "bidirectional"))
    )
    (net (code "61") (name "DO_LLC") (class "Default")
      (node (ref "IC6") (pin "12") (pinfunction "I_12") (pintype "input"))
      (node (ref "R20") (pin "1") (pinfunction "1_1") (pintype "passive"))
    )
    (net (code "62") (name "EN_M1_NOT") (class "Default")
      (node (ref "IC4") (pin "76") (pinfunction "FB6MC5_76") (pintype "bidirectional"))
      (node (ref "U1") (pin "40") (pinfunction "PL5(OC5C)_40") (pintype "bidirectional"))
    )
    (net (code "63") (name "GET_CTRL_REG") (class "Default")
      (node (ref "IC4") (pin "86") (pinfunction "FB6MC17_86") (pintype "bidirectional"))
      (node (ref "U1") (pin "46") (pinfunction "(TXD1/INT3)PD3_46") (pintype "bidirectional"))
    )
    (net (code "64") (name "GET_DATA_REG") (class "Default")
      (node (ref "IC4") (pin "85") (pinfunction "FB6MC15_85") (pintype "bidirectional"))
      (node (ref "U1") (pin "45") (pinfunction "(RXD1/INT2)PD2_45") (pintype "bidirectional"))
    )
    (net (code "65") (name "GND") (class "Default")
      (node (ref "4B") (pin "1") (pinfunction "P_1") (pintype "passive"))
      (node (ref "5B") (pin "1") (pinfunction "P_1") (pintype "passive"))
      (node (ref "C1") (pin "2") (pinfunction "2_2") (pintype "passive"))
      (node (ref "C13") (pin "2") (pinfunction "2_2") (pintype "passive"))
      (node (ref "C14") (pin "2") (pinfunction "2_2") (pintype "passive"))
      (node (ref "C15") (pin "2") (pinfunction "2_2") (pintype "passive"))
      (node (ref "C16") (pin "1") (pinfunction "1_1") (pintype "passive"))
      (node (ref "C17") (pin "1") (pinfunction "1_1") (pintype "passive"))
      (node (ref "C18") (pin "2") (pinfunction "2_2") (pintype "passive"))
      (node (ref "C19") (pin "2") (pinfunction "2_2") (pintype "passive"))
      (node (ref "C2") (pin "2") (pinfunction "2_2") (pintype "passive"))
      (node (ref "C20") (pin "1") (pinfunction "1_1") (pintype "passive"))
      (node (ref "C21") (pin "1") (pinfunction "1_1") (pintype "passive"))
      (node (ref "C3") (pin "2") (pinfunction "2_2") (pintype "passive"))
      (node (ref "C5") (pin "1") (pinfunction "1_1") (pintype "passive"))
      (node (ref "C6") (pin "2") (pinfunction "2_2") (pintype "passive"))
      (node (ref "C8") (pin "1") (pinfunction "1_1") (pintype "passive"))
      (node (ref "IC2") (pin "1") (pinfunction "GND_1") (pintype "power_in"))
      (node (ref "IC4") (pin "100") (pinfunction "GND8_100") (pintype "power_in"))
      (node (ref "IC4") (pin "21") (pinfunction "GND1_21") (pintype "power_in"))
      (node (ref "IC4") (pin "31") (pinfunction "GND2_31") (pintype "power_in"))
      (node (ref "IC4") (pin "44") (pinfunction "GND3_44") (pintype "power_in"))
      (node (ref "IC4") (pin "62") (pinfunction "GND4_62") (pintype "power_in"))
      (node (ref "IC4") (pin "69") (pinfunction "GND5_69") (pintype "power_in"))
      (node (ref "IC4") (pin "75") (pinfunction "GND6_75") (pintype "power_in"))
      (node (ref "IC4") (pin "84") (pinfunction "GND7_84") (pintype "power_in"))
      (node (ref "IC6") (pin "1") (pinfunction "OE_1") (pintype "input"))
      (node (ref "IC6") (pin "10") (pinfunction "OE_10") (pintype "input"))
      (node (ref "IC6") (pin "13") (pinfunction "OE_13") (pintype "input"))
      (node (ref "IC6") (pin "4") (pinfunction "OE_4") (pintype "input"))
      (node (ref "IC7") (pin "1") (pinfunction "GND_1") (pintype "bidirectional"))
      (node (ref "J1") (pin "5") (pinfunction "GND_5") (pintype "power_in"))
      (node (ref "J1") (pin "S1") (pinfunction "SHIELD_S1") (pintype "passive"))
      (node (ref "J1") (pin "S2") (pinfunction "SHIELD_S2") (pintype "passive"))
      (node (ref "J1") (pin "S3") (pinfunction "SHIELD_S3") (pintype "passive"))
      (node (ref "J1") (pin "S4") (pinfunction "SHIELD_S4") (pintype "passive"))
      (node (ref "J1") (pin "S5") (pinfunction "SHIELD_S5") (pintype "passive"))
      (node (ref "J1") (pin "S6") (pinfunction "SHIELD_S6") (pintype "passive"))
      (node (ref "JP2") (pin "2") (pinfunction "2_2") (pintype "passive"))
      (node (ref "JP6") (pin "6") (pinfunction "6_6") (pintype "passive"))
      (node (ref "LED2") (pin "2") (pinfunction "C_2") (pintype "bidirectional"))
      (node (ref "MICRO_SD1") (pin "6") (pinfunction "VSS_6") (pintype "power_in"))
      (node (ref "MICRO_SD1") (pin "MP1") (pinfunction "SHIELD_MP1") (pintype "power_in"))
      (node (ref "MICRO_SD1") (pin "MP2") (pinfunction "SHIELD_MP2") (pintype "power_in"))
      (node (ref "MICRO_SD1") (pin "MP3") (pinfunction "SHIELD_MP3") (pintype "power_in"))
      (node (ref "MICRO_SD1") (pin "MP4") (pinfunction "SHIELD_MP4") (pintype "power_in"))
      (node (ref "R10") (pin "1") (pinfunction "1_1") (pintype "passive"))
      (node (ref "R26") (pin "2") (pinfunction "2_2") (pintype "passive"))
      (node (ref "R8") (pin "1") (pinfunction "1_1") (pintype "passive"))
      (node (ref "R9") (pin "1") (pinfunction "1_1") (pintype "passive"))
      (node (ref "S1") (pin "1") (pinfunction "P_1") (pintype "passive"))
      (node (ref "U1") (pin "11") (pinfunction "GND_11") (pintype "power_in"))
      (node (ref "U1") (pin "32") (pinfunction "GND1_32") (pintype "power_in"))
      (node (ref "U1") (pin "62") (pinfunction "GND2_62") (pintype "power_in"))
      (node (ref "U1") (pin "81") (pinfunction "GND3_81") (pintype "power_in"))
      (node (ref "U1") (pin "99") (pinfunction "AGND_99") (pintype "power_in"))
      (node (ref "U2") (pin "16") (pinfunction "VSS_16") (pintype "output"))
    )
    (net (code "66") (name "LEDB") (class "Default")
      (node (ref "R3") (pin "1") (pinfunction "1_1") (pintype "passive"))
      (node (ref "U1") (pin "7") (pinfunction "(OC3C/INT5)PE5_7") (pintype "bidirectional"))
    )
    (net (code "67") (name "LEDG") (class "Default")
      (node (ref "R13") (pin "1") (pinfunction "1_1") (pintype "passive"))
      (node (ref "U1") (pin "1") (pinfunction "(OC0B)PG5_1") (pintype "bidirectional"))
    )
    (net (code "68") (name "LEDR") (class "Default")
      (node (ref "R2") (pin "1") (pinfunction "1_1") (pintype "passive"))
      (node (ref "U1") (pin "6") (pinfunction "(OC3B/INT4)PE4_6") (pintype "bidirectional"))
    )
    (net (code "69") (name "LE_IL") (class "Default")
      (node (ref "IC5") (pin "11") (pinfunction "C_11") (pintype "input"))
      (node (ref "U1") (pin "5") (pinfunction "(OC3A/AIN1)PE3_5") (pintype "bidirectional"))
    )
    (net (code "70") (name "LE_OL") (class "Default")
      (node (ref "IC4") (pin "72") (pinfunction "FB8MC15_72") (pintype "bidirectional"))
      (node (ref "IC9") (pin "11") (pinfunction "C_11") (pintype "input"))
    )
    (net (code "71") (name "MISO") (class "Default")
      (node (ref "IC6") (pin "11") (pinfunction "O_11") (pintype "tri_state"))
      (node (ref "JP6") (pin "1") (pinfunction "1_1") (pintype "passive"))
      (node (ref "U1") (pin "22") (pinfunction "(MISO/PCINT3)PB3_22") (pintype "bidirectional"))
    )
    (net (code "72") (name "MOSI") (class "Default")
      (node (ref "JP6") (pin "4") (pinfunction "4_4") (pintype "passive"))
      (node (ref "R17") (pin "1") (pinfunction "1_1") (pintype "passive"))
      (node (ref "U1") (pin "21") (pinfunction "(MOSI/PCINT2)PB2_21") (pintype "bidirectional"))
    )
    (net (code "73") (name "Net-(IC4-FB5MC8)") (class "Default")
      (node (ref "IC4") (pin "39") (pinfunction "FB5MC8_39") (pintype "bidirectional"))
      (node (ref "JP1") (pin "2") (pinfunction "2_2") (pintype "passive"))
    )
    (net (code "74") (name "Net-(IC4-FB6MC2)") (class "Default")
      (node (ref "IC4") (pin "74") (pinfunction "FB6MC2_74") (pintype "bidirectional"))
      (node (ref "PAD8") (pin "1") (pinfunction "P_1") (pintype "passive"))
    )
    (net (code "75") (name "Net-(IC4-FB8MC6)") (class "Default")
      (node (ref "IC4") (pin "65") (pinfunction "FB8MC6_65") (pintype "bidirectional"))
      (node (ref "PAD2") (pin "1") (pinfunction "P_1") (pintype "passive"))
    )
    (net (code "76") (name "Net-(IC4-FB8MC8)") (class "Default")
      (node (ref "IC4") (pin "66") (pinfunction "FB8MC8_66") (pintype "bidirectional"))
      (node (ref "PAD3") (pin "1") (pinfunction "P_1") (pintype "passive"))
    )
    (net (code "77") (name "Net-(IC4-FB8MC9)") (class "Default")
      (node (ref "IC4") (pin "67") (pinfunction "FB8MC9_67") (pintype "bidirectional"))
      (node (ref "PAD4") (pin "1") (pinfunction "P_1") (pintype "passive"))
    )
    (net (code "78") (name "Net-(IC4-FB8MC11)") (class "Default")
      (node (ref "IC4") (pin "68") (pinfunction "FB8MC11_68") (pintype "bidirectional"))
      (node (ref "PAD5") (pin "1") (pinfunction "P_1") (pintype "passive"))
    )
    (net (code "79") (name "Net-(IC4-FB8MC12)") (class "Default")
      (node (ref "IC4") (pin "70") (pinfunction "FB8MC12_70") (pintype "bidirectional"))
      (node (ref "PAD7") (pin "1") (pinfunction "P_1") (pintype "passive"))
    )
    (net (code "80") (name "Net-(IC4-FB8MC17)") (class "Default")
      (node (ref "IC4") (pin "73") (pinfunction "FB8MC17_73") (pintype "bidirectional"))
      (node (ref "PAD6") (pin "1") (pinfunction "P_1") (pintype "passive"))
    )
    (net (code "81") (name "Net-(IC4-GCK3)") (class "Default")
      (node (ref "IC4") (pin "27") (pinfunction "GCK3_27") (pintype "bidirectional"))
      (node (ref "PAD1") (pin "1") (pinfunction "P_1") (pintype "passive"))
    )
    (net (code "82") (name "Net-(IC6A-I)") (class "Default")
      (node (ref "IC6") (pin "2") (pinfunction "I_2") (pintype "input"))
      (node (ref "R17") (pin "2") (pinfunction "2_2") (pintype "passive"))
    )
    (net (code "83") (name "Net-(IC6B-I)") (class "Default")
      (node (ref "IC6") (pin "5") (pinfunction "I_5") (pintype "input"))
      (node (ref "R18") (pin "2") (pinfunction "2_2") (pintype "passive"))
    )
    (net (code "84") (name "Net-(IC6C-I)") (class "Default")
      (node (ref "IC6") (pin "9") (pinfunction "I_9") (pintype "input"))
      (node (ref "R21") (pin "2") (pinfunction "2_2") (pintype "passive"))
    )
    (net (code "85") (name "Net-(IC7-DTR)") (class "Default")
      (node (ref "C9") (pin "2") (pinfunction "2_2") (pintype "passive"))
      (node (ref "IC7") (pin "13") (pinfunction "DTR_13") (pintype "bidirectional"))
      (node (ref "R26") (pin "1") (pinfunction "1_1") (pintype "passive"))
    )
    (net (code "86") (name "Net-(IC7-RX)") (class "Default")
      (node (ref "IC7") (pin "3") (pinfunction "RX_3") (pintype "bidirectional"))
      (node (ref "R23") (pin "2") (pinfunction "2_2") (pintype "passive"))
    )
    (net (code "87") (name "Net-(IC7-TX)") (class "Default")
      (node (ref "IC7") (pin "2") (pinfunction "TX_2") (pintype "bidirectional"))
      (node (ref "R22") (pin "2") (pinfunction "2_2") (pintype "passive"))
    )
    (net (code "88") (name "Net-(IC7-V3)") (class "Default")
      (node (ref "C8") (pin "2") (pinfunction "2_2") (pintype "passive"))
      (node (ref "IC7") (pin "4") (pinfunction "V3_4") (pintype "bidirectional"))
    )
    (net (code "89") (name "Net-(IC7-XI)") (class "Default")
      (node (ref "C20") (pin "2") (pinfunction "2_2") (pintype "passive"))
      (node (ref "IC7") (pin "7") (pinfunction "XI_7") (pintype "bidirectional"))
      (node (ref "Q2") (pin "3") (pinfunction "2_3") (pintype "passive"))
      (node (ref "R27") (pin "2") (pinfunction "2_2") (pintype "passive"))
    )
    (net (code "90") (name "Net-(IC7-XO)") (class "Default")
      (node (ref "C21") (pin "2") (pinfunction "2_2") (pintype "passive"))
      (node (ref "IC7") (pin "8") (pinfunction "XO_8") (pintype "bidirectional"))
      (node (ref "Q2") (pin "1") (pinfunction "1_1") (pintype "passive"))
      (node (ref "R27") (pin "1") (pinfunction "1_1") (pintype "passive"))
    )
    (net (code "91") (name "Net-(J1-D+)") (class "Default")
      (node (ref "J1") (pin "3") (pinfunction "D+_3") (pintype "bidirectional"))
      (node (ref "R29") (pin "2") (pinfunction "2_2") (pintype "passive"))
    )
    (net (code "92") (name "Net-(J1-D-)") (class "Default")
      (node (ref "J1") (pin "2") (pinfunction "D-_2") (pintype "bidirectional"))
      (node (ref "R28") (pin "2") (pinfunction "2_2") (pintype "passive"))
    )
    (net (code "93") (name "Net-(LED1-PadA)") (class "Default")
      (node (ref "LED1") (pin "A") (pinfunction "A_A") (pintype "passive"))
      (node (ref "R11") (pin "2") (pinfunction "2_2") (pintype "passive"))
    )
    (net (code "94") (name "Net-(LED2-BLU)") (class "Default")
      (node (ref "LED2") (pin "4") (pinfunction "BLU_4") (pintype "bidirectional"))
      (node (ref "R3") (pin "2") (pinfunction "2_2") (pintype "passive"))
    )
    (net (code "95") (name "Net-(LED2-GRN)") (class "Default")
      (node (ref "LED2") (pin "3") (pinfunction "GRN_3") (pintype "bidirectional"))
      (node (ref "R13") (pin "2") (pinfunction "2_2") (pintype "passive"))
    )
    (net (code "96") (name "Net-(LED2-RED)") (class "Default")
      (node (ref "LED2") (pin "1") (pinfunction "RED_1") (pintype "bidirectional"))
      (node (ref "R2") (pin "2") (pinfunction "2_2") (pintype "passive"))
    )
    (net (code "97") (name "Net-(MICRO_SD1-DAT0)") (class "Default")
      (node (ref "MICRO_SD1") (pin "7") (pinfunction "DAT0_7") (pintype "bidirectional"))
      (node (ref "R20") (pin "2") (pinfunction "2_2") (pintype "passive"))
    )
    (net (code "98") (name "Net-(Q1-2)") (class "Default")
      (node (ref "C16") (pin "2") (pinfunction "2_2") (pintype "passive"))
      (node (ref "Q1") (pin "3") (pinfunction "2_3") (pintype "passive"))
      (node (ref "R19") (pin "2") (pinfunction "2_2") (pintype "passive"))
      (node (ref "U1") (pin "33") (pinfunction "XTAL2_33") (pintype "output"))
    )
    (net (code "99") (name "Net-(U1-XTAL1)") (class "Default")
      (node (ref "C17") (pin "2") (pinfunction "2_2") (pintype "passive"))
      (node (ref "Q1") (pin "1") (pinfunction "1_1") (pintype "passive"))
      (node (ref "R19") (pin "1") (pinfunction "1_1") (pintype "passive"))
      (node (ref "U1") (pin "34") (pinfunction "XTAL1_34") (pintype "input"))
    )
    (net (code "100") (name "O0") (class "Default")
      (node (ref "IC5") (pin "2") (pinfunction "1D_2") (pintype "input"))
      (node (ref "U1") (pin "89") (pinfunction "PK0(ADC8/PCINT16)_89") (pintype "bidirectional"))
    )
    (net (code "101") (name "O1") (class "Default")
      (node (ref "IC5") (pin "3") (pinfunction "2D_3") (pintype "input"))
      (node (ref "U1") (pin "88") (pinfunction "PK1(ADC9/PCINT17)_88") (pintype "bidirectional"))
    )
    (net (code "102") (name "O2") (class "Default")
      (node (ref "IC5") (pin "4") (pinfunction "3D_4") (pintype "input"))
      (node (ref "U1") (pin "87") (pinfunction "PK2(ADC10/PCINT18)_87") (pintype "bidirectional"))
    )
    (net (code "103") (name "O3") (class "Default")
      (node (ref "IC5") (pin "5") (pinfunction "4D_5") (pintype "input"))
      (node (ref "U1") (pin "86") (pinfunction "PK3(ADC11/PCINT19)_86") (pintype "bidirectional"))
    )
    (net (code "104") (name "O4") (class "Default")
      (node (ref "IC5") (pin "6") (pinfunction "5D_6") (pintype "input"))
      (node (ref "U1") (pin "85") (pinfunction "PK4(ADC12/PCINT20)_85") (pintype "bidirectional"))
    )
    (net (code "105") (name "O5") (class "Default")
      (node (ref "IC5") (pin "7") (pinfunction "6D_7") (pintype "input"))
      (node (ref "U1") (pin "84") (pinfunction "PK5(ADC13/PCINT21)_84") (pintype "bidirectional"))
    )
    (net (code "106") (name "O6") (class "Default")
      (node (ref "IC5") (pin "8") (pinfunction "7D_8") (pintype "input"))
      (node (ref "U1") (pin "83") (pinfunction "PK6(ADC14/PCINT22)_83") (pintype "bidirectional"))
    )
    (net (code "107") (name "O7") (class "Default")
      (node (ref "IC5") (pin "9") (pinfunction "8D_9") (pintype "input"))
      (node (ref "U1") (pin "82") (pinfunction "PK7(ADC15/PCINT23)_82") (pintype "bidirectional"))
    )
    (net (code "108") (name "OE_OL") (class "Default")
      (node (ref "IC9") (pin "1") (pinfunction "OC_1") (pintype "input"))
      (node (ref "U1") (pin "13") (pinfunction "PH1(TXD2)_13") (pintype "bidirectional"))
    )
    (net (code "109") (name "PAGE_A8") (class "Default")
      (node (ref "IC4") (pin "80") (pinfunction "FB6MC11_80") (pintype "bidirectional"))
      (node (ref "U1") (pin "41") (pinfunction "PL6_41") (pintype "bidirectional"))
    )
    (net (code "110") (name "RD+") (class "Default")
      (node (ref "IC7") (pin "5") (pinfunction "D+_5") (pintype "bidirectional"))
      (node (ref "R29") (pin "1") (pinfunction "1_1") (pintype "passive"))
    )
    (net (code "111") (name "RD-") (class "Default")
      (node (ref "IC7") (pin "6") (pinfunction "D-_6") (pintype "bidirectional"))
      (node (ref "R28") (pin "1") (pinfunction "1_1") (pintype "passive"))
    )
    (net (code "112") (name "RESET") (class "Default")
      (node (ref "C5") (pin "2") (pinfunction "2_2") (pintype "passive"))
      (node (ref "C9") (pin "1") (pinfunction "1_1") (pintype "passive"))
      (node (ref "D1") (pin "A") (pinfunction "A_A") (pintype "passive"))
      (node (ref "JP6") (pin "5") (pinfunction "5_5") (pintype "passive"))
      (node (ref "R15") (pin "1") (pinfunction "1_1") (pintype "passive"))
      (node (ref "S1") (pin "2") (pinfunction "S_2") (pintype "passive"))
      (node (ref "U1") (pin "30") (pinfunction "RESET_30") (pintype "input"))
    )
    (net (code "113") (name "ROM_WR_EN") (class "Default")
      (node (ref "IC4") (pin "79") (pinfunction "FB6MC9_79") (pintype "bidirectional"))
      (node (ref "U1") (pin "36") (pinfunction "PL1(ICP5)_36") (pintype "bidirectional"))
    )
    (net (code "114") (name "RST_CTRL_REG") (class "Default")
      (node (ref "IC4") (pin "82") (pinfunction "FB6MC14_82") (pintype "bidirectional"))
      (node (ref "U1") (pin "26") (pinfunction "(OC0A/OC1C/PCINT7)PB7_26") (pintype "bidirectional"))
    )
    (net (code "115") (name "RST_DATA_REG") (class "Default")
      (node (ref "IC4") (pin "81") (pinfunction "FB6MC12_81") (pintype "bidirectional"))
      (node (ref "U1") (pin "63") (pinfunction "PJ0(RXD3/PCINT9)_63") (pintype "bidirectional"))
    )
    (net (code "116") (name "RX0") (class "Default")
      (node (ref "R23") (pin "1") (pinfunction "1_1") (pintype "passive"))
      (node (ref "U1") (pin "2") (pinfunction "(RXD0/PCIN8)PE0_2") (pintype "bidirectional"))
    )
    (net (code "117") (name "SCK_LLS") (class "Default")
      (node (ref "IC6") (pin "6") (pinfunction "O_6") (pintype "tri_state"))
      (node (ref "MICRO_SD1") (pin "5") (pinfunction "CLK_5") (pintype "bidirectional"))
    )
    (net (code "118") (name "SCLK") (class "Default")
      (node (ref "JP6") (pin "3") (pinfunction "3_3") (pintype "passive"))
      (node (ref "R18") (pin "1") (pinfunction "1_1") (pintype "passive"))
      (node (ref "U1") (pin "20") (pinfunction "(SCK/PCINT1)PB1_20") (pintype "bidirectional"))
    )
    (net (code "119") (name "SD_LED") (class "Default")
      (node (ref "LED1") (pin "K") (pinfunction "C_K") (pintype "passive"))
      (node (ref "U1") (pin "37") (pinfunction "PL2(T5)_37") (pintype "bidirectional"))
    )
    (net (code "120") (name "SEL_128CHARS") (class "Default")
      (node (ref "IC4") (pin "78") (pinfunction "FB6MC8_78") (pintype "bidirectional"))
      (node (ref "U1") (pin "35") (pinfunction "PL0(ICP4)_35") (pintype "bidirectional"))
    )
    (net (code "121") (name "SPARE1") (class "Default")
      (node (ref "IC4") (pin "77") (pinfunction "FB6MC6_77") (pintype "bidirectional"))
      (node (ref "U1") (pin "38") (pinfunction "PL3(OC5A)_38") (pintype "bidirectional"))
    )
    (net (code "122") (name "SS_SD") (class "Default")
      (node (ref "R21") (pin "1") (pinfunction "1_1") (pintype "passive"))
      (node (ref "U1") (pin "19") (pinfunction "(SS/PCINT0)PB0_19") (pintype "bidirectional"))
    )
    (net (code "123") (name "TCK") (class "Default")
      (node (ref "IC4") (pin "48") (pinfunction "TCK_48") (pintype "passive"))
      (node (ref "JP3") (pin "1") (pinfunction "1_1") (pintype "passive"))
      (node (ref "R7") (pin "2") (pinfunction "2_2") (pintype "passive"))
      (node (ref "R8") (pin "2") (pinfunction "2_2") (pintype "passive"))
    )
    (net (code "124") (name "TCK'") (class "Default")
      (node (ref "R7") (pin "1") (pinfunction "1_1") (pintype "passive"))
      (node (ref "U1") (pin "24") (pinfunction "(OC1A/PCINT5)PB5_24") (pintype "bidirectional"))
    )
    (net (code "125") (name "TDI") (class "Default")
      (node (ref "IC4") (pin "45") (pinfunction "TDI_45") (pintype "passive"))
      (node (ref "JP3") (pin "3") (pinfunction "3_3") (pintype "passive"))
      (node (ref "R5") (pin "2") (pinfunction "2_2") (pintype "passive"))
      (node (ref "R9") (pin "2") (pinfunction "2_2") (pintype "passive"))
    )
    (net (code "126") (name "TDI'") (class "Default")
      (node (ref "R5") (pin "1") (pinfunction "1_1") (pintype "passive"))
      (node (ref "U1") (pin "18") (pinfunction "PH6(OC2B)_18") (pintype "bidirectional"))
    )
    (net (code "127") (name "TDO") (class "Default")
      (node (ref "IC4") (pin "83") (pinfunction "TDO_83") (pintype "passive"))
      (node (ref "JP3") (pin "2") (pinfunction "2_2") (pintype "passive"))
      (node (ref "R6") (pin "2") (pinfunction "2_2") (pintype "passive"))
    )
    (net (code "128") (name "TDO'") (class "Default")
      (node (ref "R6") (pin "1") (pinfunction "1_1") (pintype "passive"))
      (node (ref "U1") (pin "17") (pinfunction "PH5(OC4C)_17") (pintype "bidirectional"))
    )
    (net (code "129") (name "TMS") (class "Default")
      (node (ref "IC4") (pin "47") (pinfunction "TMS_47") (pintype "passive"))
      (node (ref "JP3") (pin "4") (pinfunction "4_4") (pintype "passive"))
      (node (ref "R10") (pin "2") (pinfunction "2_2") (pintype "passive"))
      (node (ref "R4") (pin "2") (pinfunction "2_2") (pintype "passive"))
    )
    (net (code "130") (name "TMS'") (class "Default")
      (node (ref "R4") (pin "1") (pinfunction "1_1") (pintype "passive"))
      (node (ref "U1") (pin "23") (pinfunction "(OC2A/PCINT4)PB4_23") (pintype "bidirectional"))
    )
    (net (code "131") (name "TX0") (class "Default")
      (node (ref "R22") (pin "1") (pinfunction "1_1") (pintype "passive"))
      (node (ref "U1") (pin "3") (pinfunction "(TXD0)PE1_3") (pintype "bidirectional"))
    )
    (net (code "132") (name "VCC") (class "Default")
      (node (ref "1B") (pin "1") (pinfunction "P_1") (pintype "passive"))
      (node (ref "C1") (pin "1") (pinfunction "1_1") (pintype "passive"))
      (node (ref "C13") (pin "1") (pinfunction "1_1") (pintype "passive"))
      (node (ref "C14") (pin "1") (pinfunction "1_1") (pintype "passive"))
      (node (ref "C15") (pin "1") (pinfunction "1_1") (pintype "passive"))
      (node (ref "C19") (pin "1") (pinfunction "1_1") (pintype "passive"))
      (node (ref "C2") (pin "1") (pinfunction "1_1") (pintype "passive"))
      (node (ref "C3") (pin "1") (pinfunction "1_1") (pintype "passive"))
      (node (ref "D1") (pin "C") (pinfunction "C_C") (pintype "passive"))
      (node (ref "IC2") (pin "3") (pinfunction "VIN_3") (pintype "input"))
      (node (ref "IC3") (pin "12") (pinfunction "I_12") (pintype "input"))
      (node (ref "IC3") (pin "13") (pinfunction "OE_13") (pintype "input"))
      (node (ref "IC3") (pin "2") (pinfunction "I_2") (pintype "input"))
      (node (ref "IC3") (pin "5") (pinfunction "I_5") (pintype "input"))
      (node (ref "IC7") (pin "16") (pinfunction "VCC_16") (pintype "bidirectional"))
      (node (ref "J1") (pin "1") (pinfunction "VBUS_1") (pintype "power_in"))
      (node (ref "JP6") (pin "2") (pinfunction "2_2") (pintype "passive"))
      (node (ref "R11") (pin "1") (pinfunction "1_1") (pintype "passive"))
      (node (ref "R15") (pin "2") (pinfunction "2_2") (pintype "passive"))
      (node (ref "U1") (pin "10") (pinfunction "VCC_10") (pintype "power_in"))
      (node (ref "U1") (pin "100") (pinfunction "AVCC_100") (pintype "power_in"))
      (node (ref "U1") (pin "31") (pinfunction "VCC1_31") (pintype "power_in"))
      (node (ref "U1") (pin "61") (pinfunction "VCC2_61") (pintype "power_in"))
      (node (ref "U1") (pin "80") (pinfunction "VCC3_80") (pintype "power_in"))
      (node (ref "U2") (pin "32") (pinfunction "VCC_32") (pintype "power_in"))
    )
    (net (code "133") (name "unconnected-(IC3D-O-Pad11)") (class "Default")
      (node (ref "IC3") (pin "11") (pinfunction "O_11") (pintype "tri_state"))
    )
    (net (code "134") (name "unconnected-(IC7-CTS-Pad9)") (class "Default")
      (node (ref "IC7") (pin "9") (pinfunction "CTS_9") (pintype "bidirectional"))
    )
    (net (code "135") (name "unconnected-(IC7-DCD-Pad12)") (class "Default")
      (node (ref "IC7") (pin "12") (pinfunction "DCD_12") (pintype "bidirectional"))
    )
    (net (code "136") (name "unconnected-(IC7-DSR-Pad10)") (class "Default")
      (node (ref "IC7") (pin "10") (pinfunction "DSR_10") (pintype "bidirectional"))
    )
    (net (code "137") (name "unconnected-(IC7-RI-Pad11)") (class "Default")
      (node (ref "IC7") (pin "11") (pinfunction "RI_11") (pintype "bidirectional"))
    )
    (net (code "138") (name "unconnected-(IC7-RS232-Pad15)") (class "Default")
      (node (ref "IC7") (pin "15") (pinfunction "RS232_15") (pintype "bidirectional"))
    )
    (net (code "139") (name "unconnected-(IC7-RTS-Pad14)") (class "Default")
      (node (ref "IC7") (pin "14") (pinfunction "RTS_14") (pintype "bidirectional"))
    )
    (net (code "140") (name "unconnected-(J1-ID-Pad4)") (class "Default")
      (node (ref "J1") (pin "4") (pinfunction "ID_4") (pintype "bidirectional"))
    )
    (net (code "141") (name "unconnected-(MICRO_SD1-CD-PadCD1)") (class "Default")
      (node (ref "MICRO_SD1") (pin "CD1") (pinfunction "CD_CD1") (pintype "passive"))
    )
    (net (code "142") (name "unconnected-(MICRO_SD1-DAT1-Pad8)") (class "Default")
      (node (ref "MICRO_SD1") (pin "8") (pinfunction "DAT1_8") (pintype "bidirectional"))
    )
    (net (code "143") (name "unconnected-(MICRO_SD1-DAT2-Pad1)") (class "Default")
      (node (ref "MICRO_SD1") (pin "1") (pinfunction "DAT2_1") (pintype "bidirectional"))
    )
    (net (code "144") (name "unconnected-(U1-(CLKO{slash}ICP3{slash}INT7)PE7-Pad9)") (class "Default")
      (node (ref "U1") (pin "9") (pinfunction "(CLKO/ICP3/INT7)PE7_9") (pintype "bidirectional"))
    )
    (net (code "145") (name "unconnected-(U1-(ICP1)PD4-Pad47)") (class "Default")
      (node (ref "U1") (pin "47") (pinfunction "(ICP1)PD4_47") (pintype "bidirectional"))
    )
    (net (code "146") (name "unconnected-(U1-(T1)PD6-Pad49)") (class "Default")
      (node (ref "U1") (pin "49") (pinfunction "(T1)PD6_49") (pintype "bidirectional"))
    )
    (net (code "147") (name "unconnected-(U1-(T3{slash}INT6)PE6-Pad8)") (class "Default")
      (node (ref "U1") (pin "8") (pinfunction "(T3/INT6)PE6_8") (pintype "bidirectional"))
    )
    (net (code "148") (name "unconnected-(U1-(TOSC1)PG4-Pad29)") (class "Default")
      (node (ref "U1") (pin "29") (pinfunction "(TOSC1)PG4_29") (pintype "bidirectional"))
    )
    (net (code "149") (name "unconnected-(U1-(TOSC2)PG3-Pad28)") (class "Default")
      (node (ref "U1") (pin "28") (pinfunction "(TOSC2)PG3_28") (pintype "bidirectional"))
    )
    (net (code "150") (name "unconnected-(U1-(XCK0{slash}AIN0)PE2-Pad4)") (class "Default")
      (node (ref "U1") (pin "4") (pinfunction "(XCK0/AIN0)PE2_4") (pintype "bidirectional"))
    )
    (net (code "151") (name "unconnected-(U1-(XCK1)PD5-Pad48)") (class "Default")
      (node (ref "U1") (pin "48") (pinfunction "(XCK1)PD5_48") (pintype "bidirectional"))
    )
    (net (code "152") (name "unconnected-(U1-PH2(XCK2)-Pad14)") (class "Default")
      (node (ref "U1") (pin "14") (pinfunction "PH2(XCK2)_14") (pintype "bidirectional"))
    )
    (net (code "153") (name "unconnected-(U1-PH7(T4)-Pad27)") (class "Default")
      (node (ref "U1") (pin "27") (pinfunction "PH7(T4)_27") (pintype "bidirectional"))
    )
    (net (code "154") (name "unconnected-(U1-PJ2(XCK3{slash}PCINT11)-Pad65)") (class "Default")
      (node (ref "U1") (pin "65") (pinfunction "PJ2(XCK3/PCINT11)_65") (pintype "bidirectional"))
    )
    (net (code "155") (name "unconnected-(U1-PJ3(PCINT12)-Pad66)") (class "Default")
      (node (ref "U1") (pin "66") (pinfunction "PJ3(PCINT12)_66") (pintype "bidirectional"))
    )
    (net (code "156") (name "unconnected-(U1-PJ4(PCINT13)-Pad67)") (class "Default")
      (node (ref "U1") (pin "67") (pinfunction "PJ4(PCINT13)_67") (pintype "bidirectional"))
    )
    (net (code "157") (name "unconnected-(U1-PJ5(PCINT14)-Pad68)") (class "Default")
      (node (ref "U1") (pin "68") (pinfunction "PJ5(PCINT14)_68") (pintype "bidirectional"))
    )
    (net (code "158") (name "unconnected-(U1-PJ6(PCINT15)-Pad69)") (class "Default")
      (node (ref "U1") (pin "69") (pinfunction "PJ6(PCINT15)_69") (pintype "bidirectional"))
    )
    (net (code "159") (name "unconnected-(U1-PJ7-Pad79)") (class "Default")
      (node (ref "U1") (pin "79") (pinfunction "PJ7_79") (pintype "bidirectional"))
    )
    (net (code "160") (name "{slash}BUSAK") (class "Default")
      (node (ref "18A") (pin "1") (pinfunction "P_1") (pintype "passive"))
      (node (ref "IC4") (pin "54") (pinfunction "FB7MC8_54") (pintype "bidirectional"))
    )
    (net (code "161") (name "{slash}BUSRQ") (class "Default")
      (node (ref "20A") (pin "1") (pinfunction "P_1") (pintype "passive"))
      (node (ref "IC4") (pin "59") (pinfunction "FB7MC14_59") (pintype "bidirectional"))
    )
    (net (code "162") (name "{slash}CLOCK") (class "Default")
      (node (ref "6B") (pin "1") (pinfunction "P_1") (pintype "passive"))
      (node (ref "IC4") (pin "22") (pinfunction "GCK1_22") (pintype "bidirectional"))
    )
    (net (code "163") (name "{slash}HALT") (class "Default")
      (node (ref "13A") (pin "1") (pinfunction "P_1") (pintype "passive"))
      (node (ref "JP1") (pin "1") (pinfunction "1_1") (pintype "passive"))
    )
    (net (code "164") (name "{slash}IORQ") (class "Default")
      (node (ref "15A") (pin "1") (pinfunction "P_1") (pintype "passive"))
      (node (ref "IC4") (pin "43") (pinfunction "FB5MC14_43") (pintype "bidirectional"))
    )
    (net (code "165") (name "{slash}M1") (class "Default")
      (node (ref "22A") (pin "1") (pinfunction "P_1") (pintype "passive"))
      (node (ref "IC4") (pin "61") (pinfunction "FB7MC17_61") (pintype "bidirectional"))
    )
    (net (code "166") (name "{slash}MEM_CE") (class "Default")
      (node (ref "IC4") (pin "97") (pinfunction "FB4MC17_97") (pintype "bidirectional"))
      (node (ref "U1") (pin "50") (pinfunction "(T0)PD7_50") (pintype "bidirectional"))
      (node (ref "U2") (pin "22") (pinfunction "CE_22") (pintype "input"))
    )
    (net (code "167") (name "{slash}MEM_OE") (class "Default")
      (node (ref "IC4") (pin "12") (pinfunction "FB1MC3_12") (pintype "bidirectional"))
      (node (ref "U1") (pin "52") (pinfunction "(RD)PG1_52") (pintype "bidirectional"))
      (node (ref "U2") (pin "24") (pinfunction "OE_24") (pintype "input"))
    )
    (net (code "168") (name "{slash}MREQ") (class "Default")
      (node (ref "14A") (pin "1") (pinfunction "P_1") (pintype "passive"))
      (node (ref "IC4") (pin "41") (pinfunction "FB5MC11_41") (pintype "bidirectional"))
    )
    (net (code "169") (name "{slash}NMI") (class "Default")
      (node (ref "12A") (pin "1") (pinfunction "P_1") (pintype "passive"))
      (node (ref "IC4") (pin "36") (pinfunction "FB5MC5_36") (pintype "bidirectional"))
    )
    (net (code "170") (name "{slash}OE_CTRL_CLOCK") (class "Default")
      (node (ref "IC3") (pin "10") (pinfunction "OE_10") (pintype "input"))
      (node (ref "IC4") (pin "10") (pinfunction "FB2MC17_10") (pintype "bidirectional"))
    )
    (net (code "171") (name "{slash}OE_IL") (class "Default")
      (node (ref "IC4") (pin "15") (pinfunction "FB1MC8_15") (pintype "bidirectional"))
      (node (ref "IC5") (pin "1") (pinfunction "OC_1") (pintype "input"))
    )
    (net (code "172") (name "{slash}OE_RAMCS") (class "Default")
      (node (ref "IC3") (pin "4") (pinfunction "OE_4") (pintype "input"))
      (node (ref "IC4") (pin "17") (pinfunction "FB1MC11_17") (pintype "bidirectional"))
    )
    (net (code "173") (name "{slash}OE_ROMCS") (class "Default")
      (node (ref "IC3") (pin "1") (pinfunction "OE_1") (pintype "input"))
      (node (ref "IC4") (pin "14") (pinfunction "FB1MC6_14") (pintype "bidirectional"))
    )
    (net (code "174") (name "{slash}RAMCS") (class "Default")
      (node (ref "2A") (pin "1") (pinfunction "P_1") (pintype "passive"))
      (node (ref "IC3") (pin "6") (pinfunction "O_6") (pintype "tri_state"))
    )
    (net (code "175") (name "{slash}RD") (class "Default")
      (node (ref "16A") (pin "1") (pinfunction "P_1") (pintype "passive"))
      (node (ref "IC4") (pin "49") (pinfunction "FB5MC17_49") (pintype "bidirectional"))
    )
    (net (code "176") (name "{slash}RESET") (class "Default")
      (node (ref "21A") (pin "1") (pinfunction "P_1") (pintype "passive"))
      (node (ref "IC4") (pin "71") (pinfunction "FB8MC14_71") (pintype "bidirectional"))
      (node (ref "U1") (pin "15") (pinfunction "PH3(OC4A)_15") (pintype "bidirectional"))
    )
    (net (code "177") (name "{slash}RFSH") (class "Default")
      (node (ref "23A") (pin "1") (pinfunction "P_1") (pintype "passive"))
      (node (ref "IC4") (pin "64") (pinfunction "FB8MC5_64") (pintype "bidirectional"))
    )
    (net (code "178") (name "{slash}ROMCS") (class "Default")
      (node (ref "23B") (pin "1") (pinfunction "P_1") (pintype "passive"))
      (node (ref "IC3") (pin "3") (pinfunction "O_3") (pintype "tri_state"))
    )
    (net (code "179") (name "{slash}WAIT") (class "Default")
      (node (ref "19A") (pin "1") (pinfunction "P_1") (pintype "passive"))
      (node (ref "IC4") (pin "56") (pinfunction "FB7MC11_56") (pintype "bidirectional"))
      (node (ref "U1") (pin "42") (pinfunction "PL7_42") (pintype "bidirectional"))
    )
    (net (code "180") (name "{slash}WR") (class "Default")
      (node (ref "17A") (pin "1") (pinfunction "P_1") (pintype "passive"))
      (node (ref "IC4") (pin "52") (pinfunction "FB7MC5_52") (pintype "bidirectional"))
    )
    (net (code "181") (name "{slash}WR'") (class "Default")
      (node (ref "IC4") (pin "13") (pinfunction "FB1MC5_13") (pintype "bidirectional"))
      (node (ref "U1") (pin "51") (pinfunction "(WR)PG0_51") (pintype "bidirectional"))
      (node (ref "U2") (pin "29") (pinfunction "WE_29") (pintype "input"))
    )
  )
)
